# RASPILOTv1_0.net
KiCad netlist of a schematic drawn in EAGLE
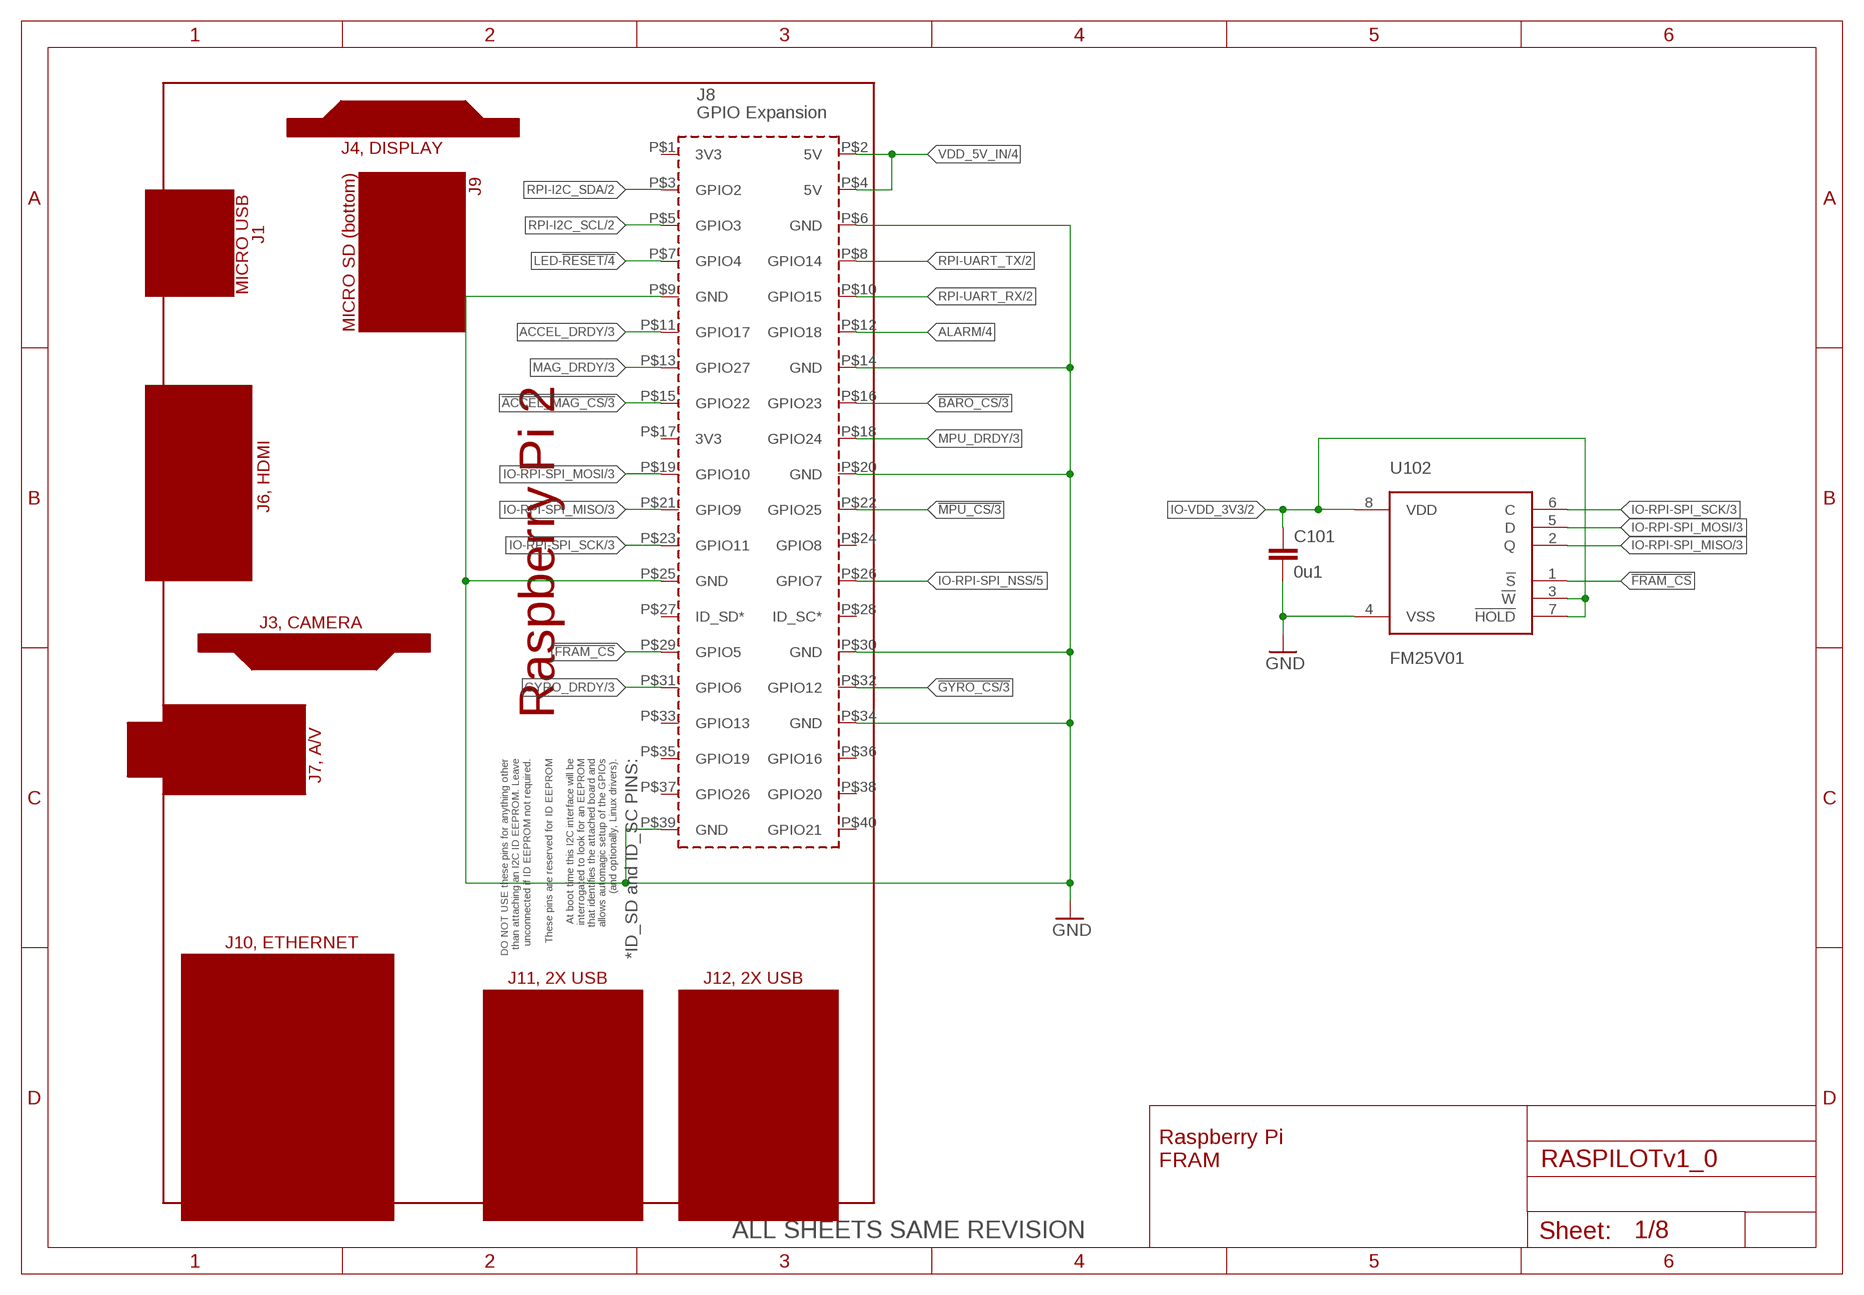
[diagram p0: schematic, sheet 1]
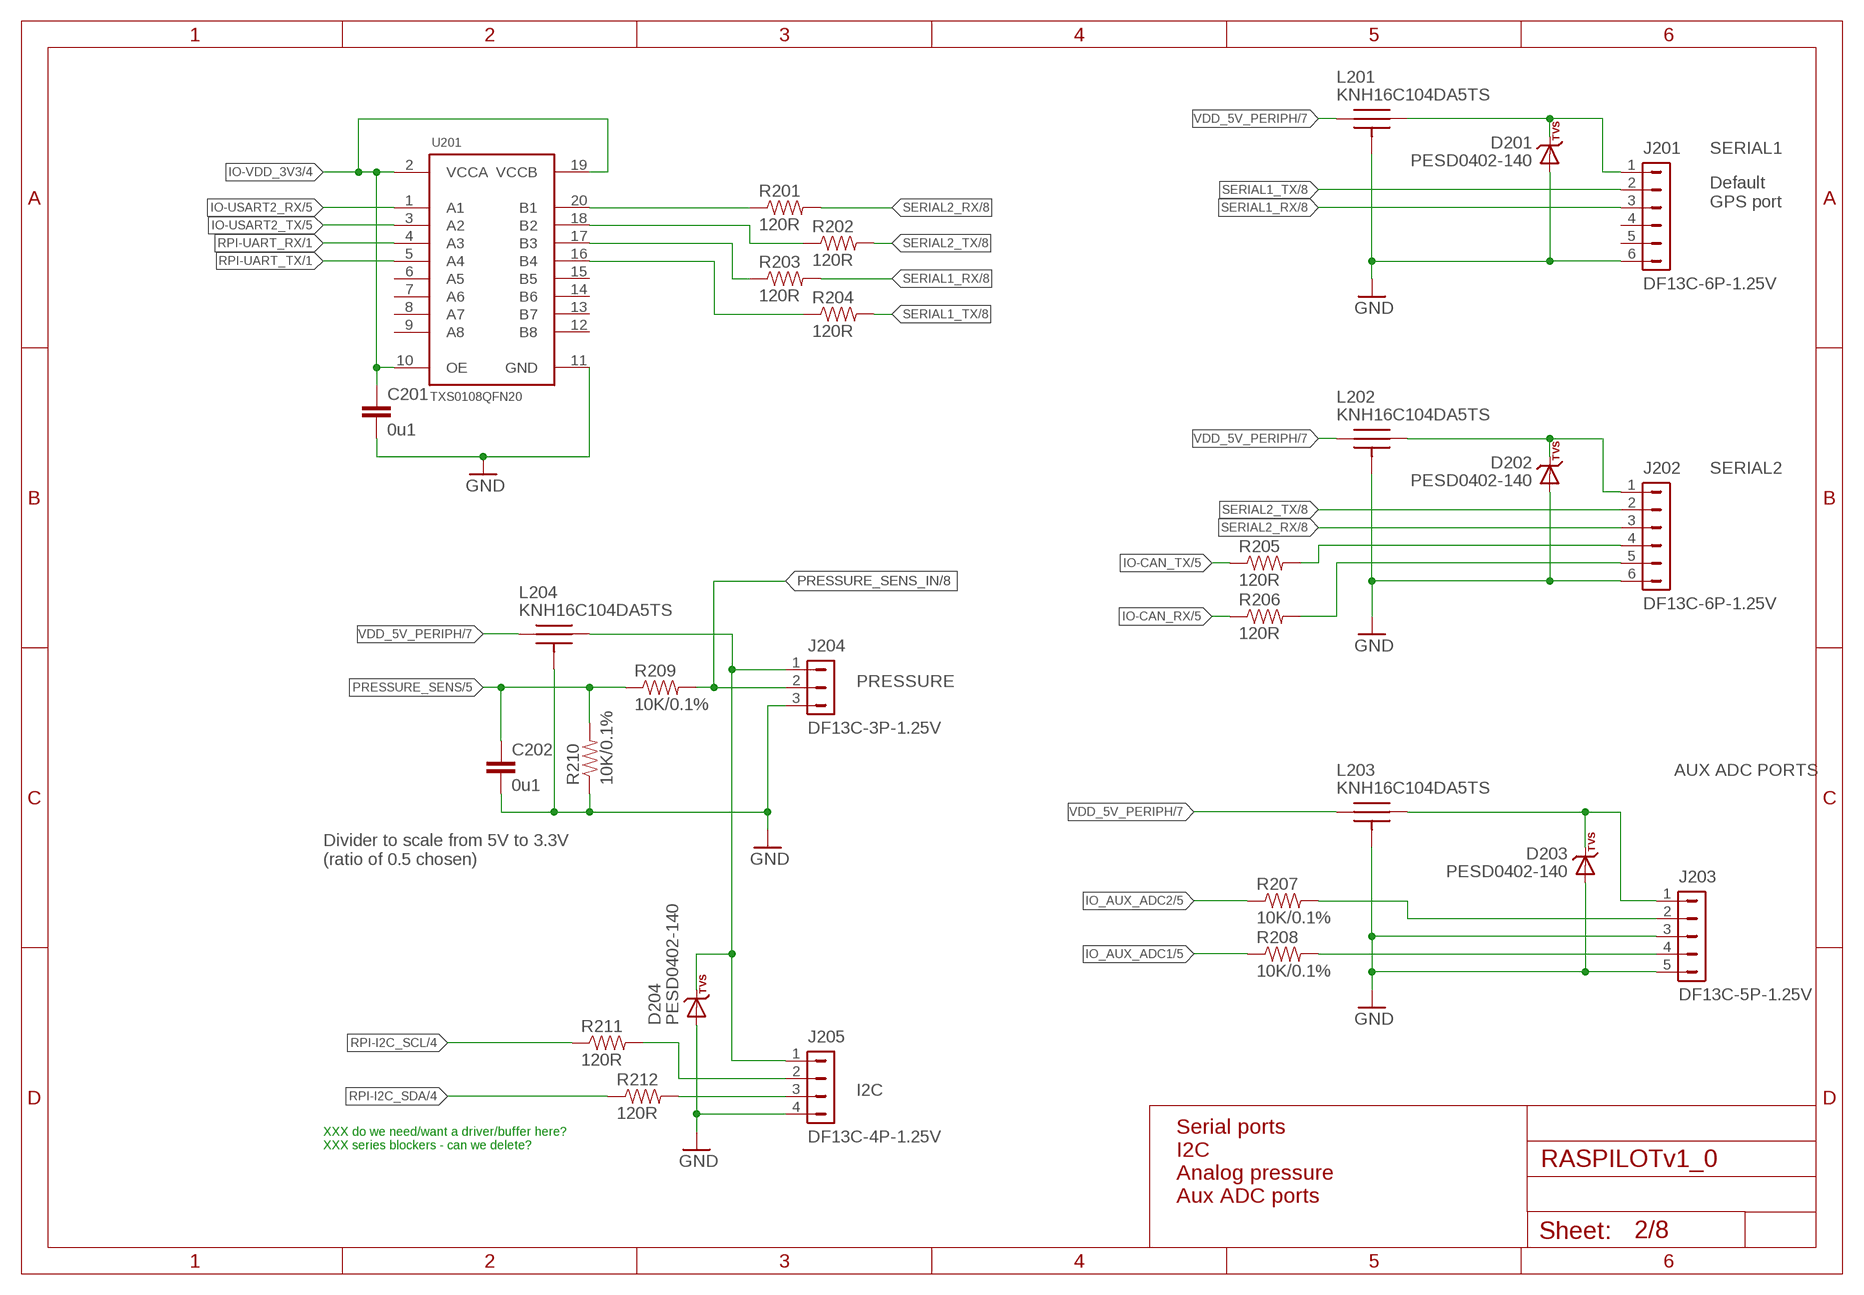
[diagram p1: schematic, sheet 2]
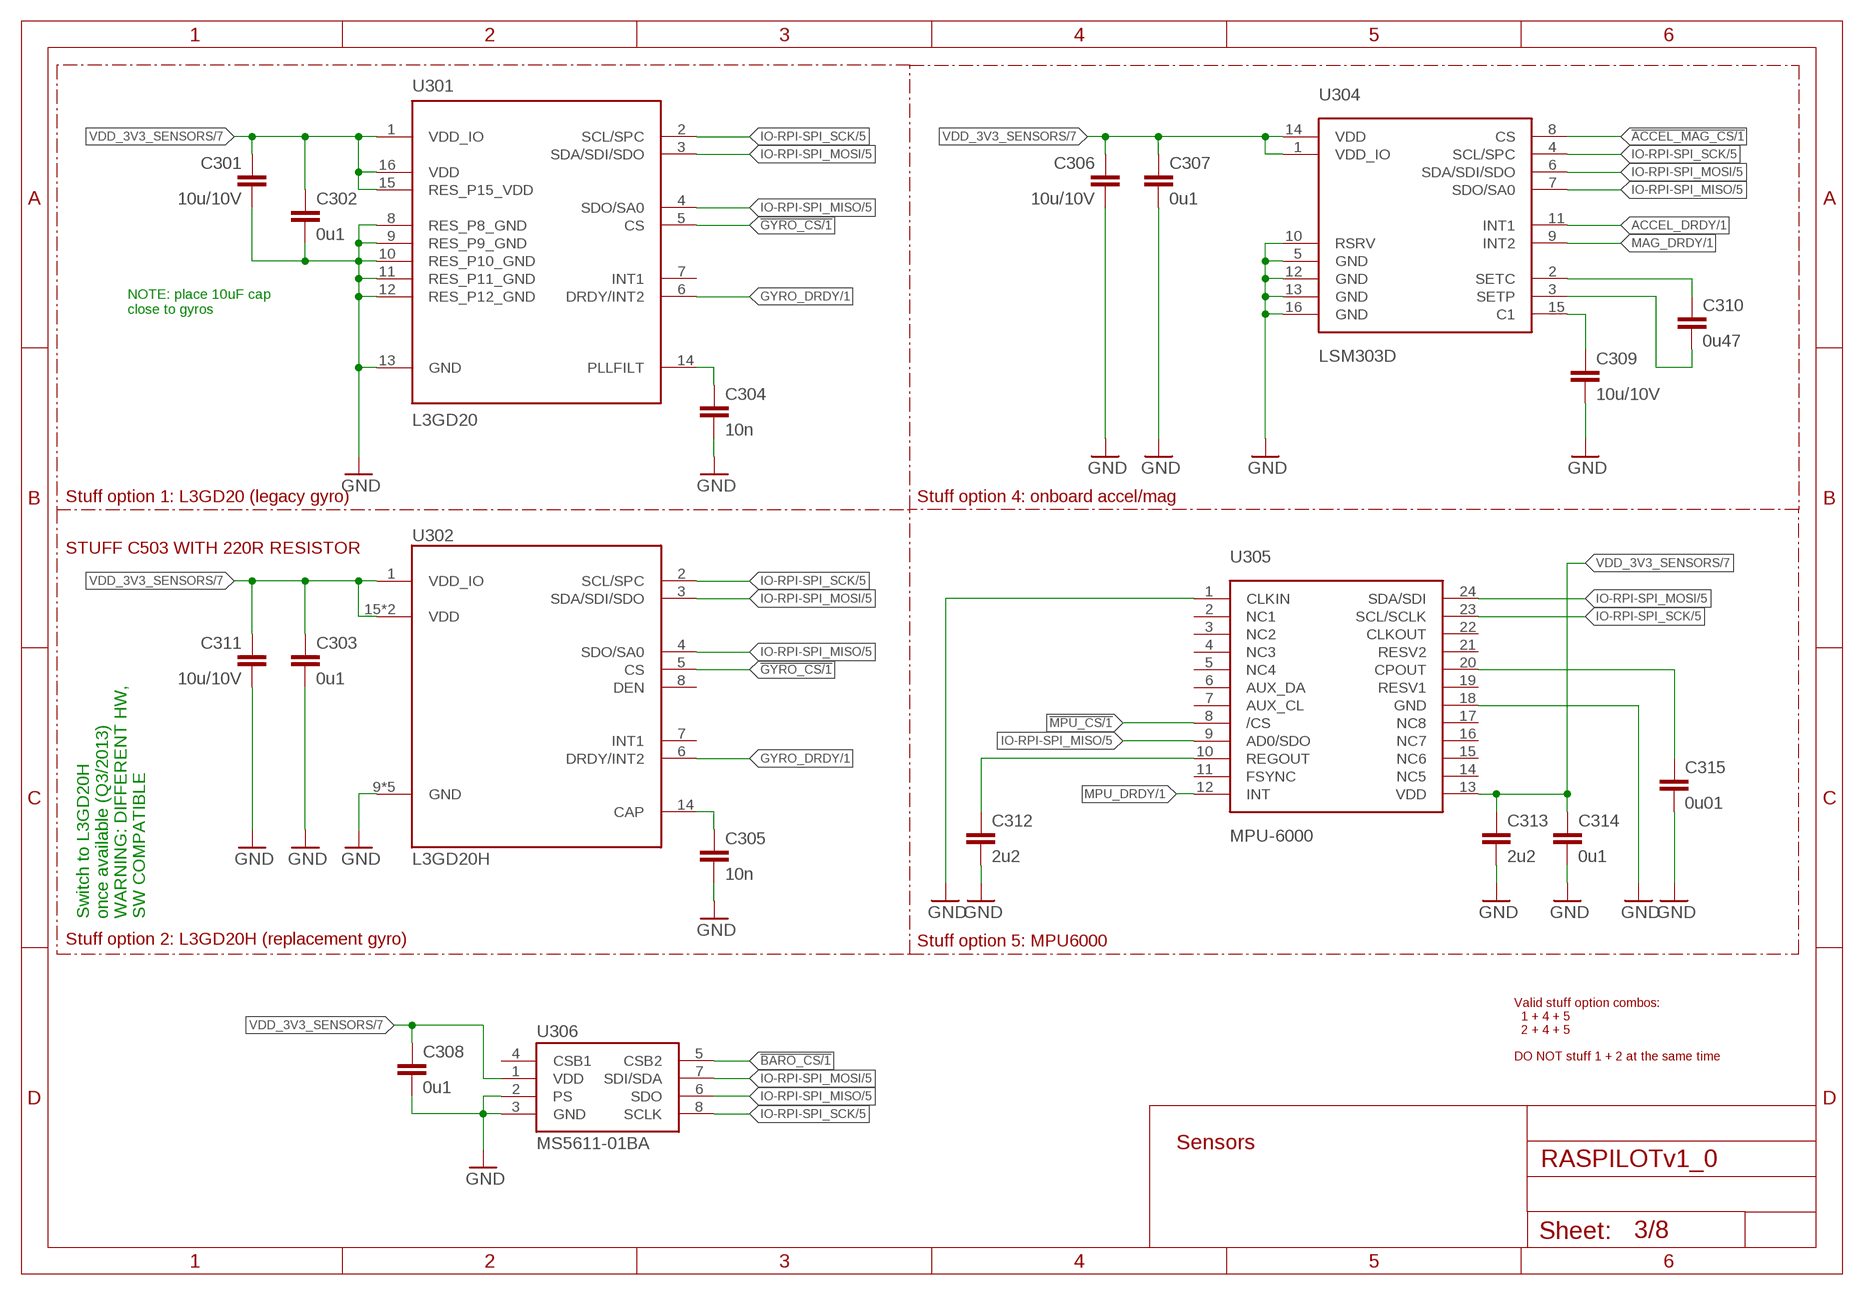
[diagram p2: schematic, sheet 3]
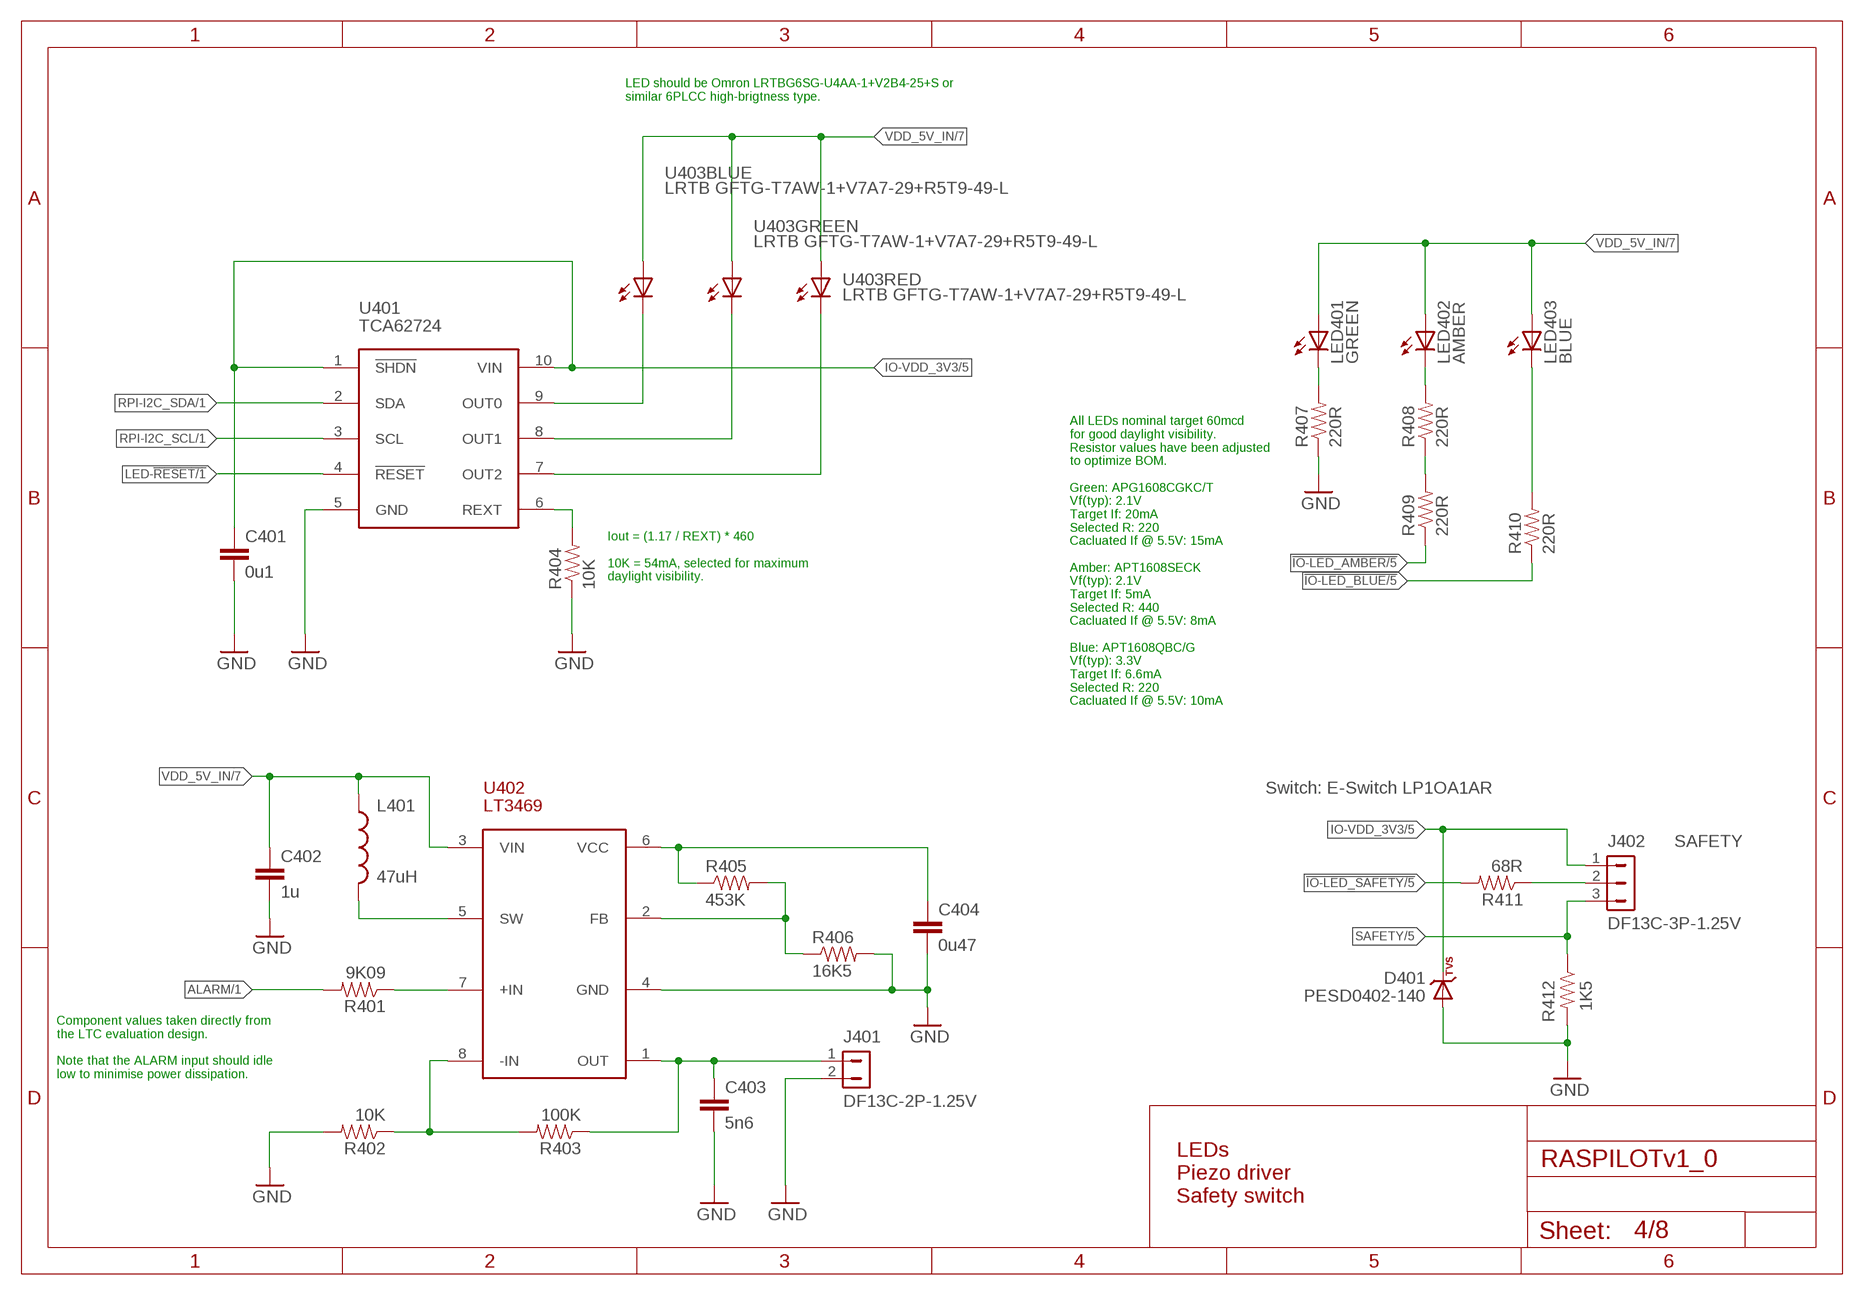
[diagram p3: schematic, sheet 4]
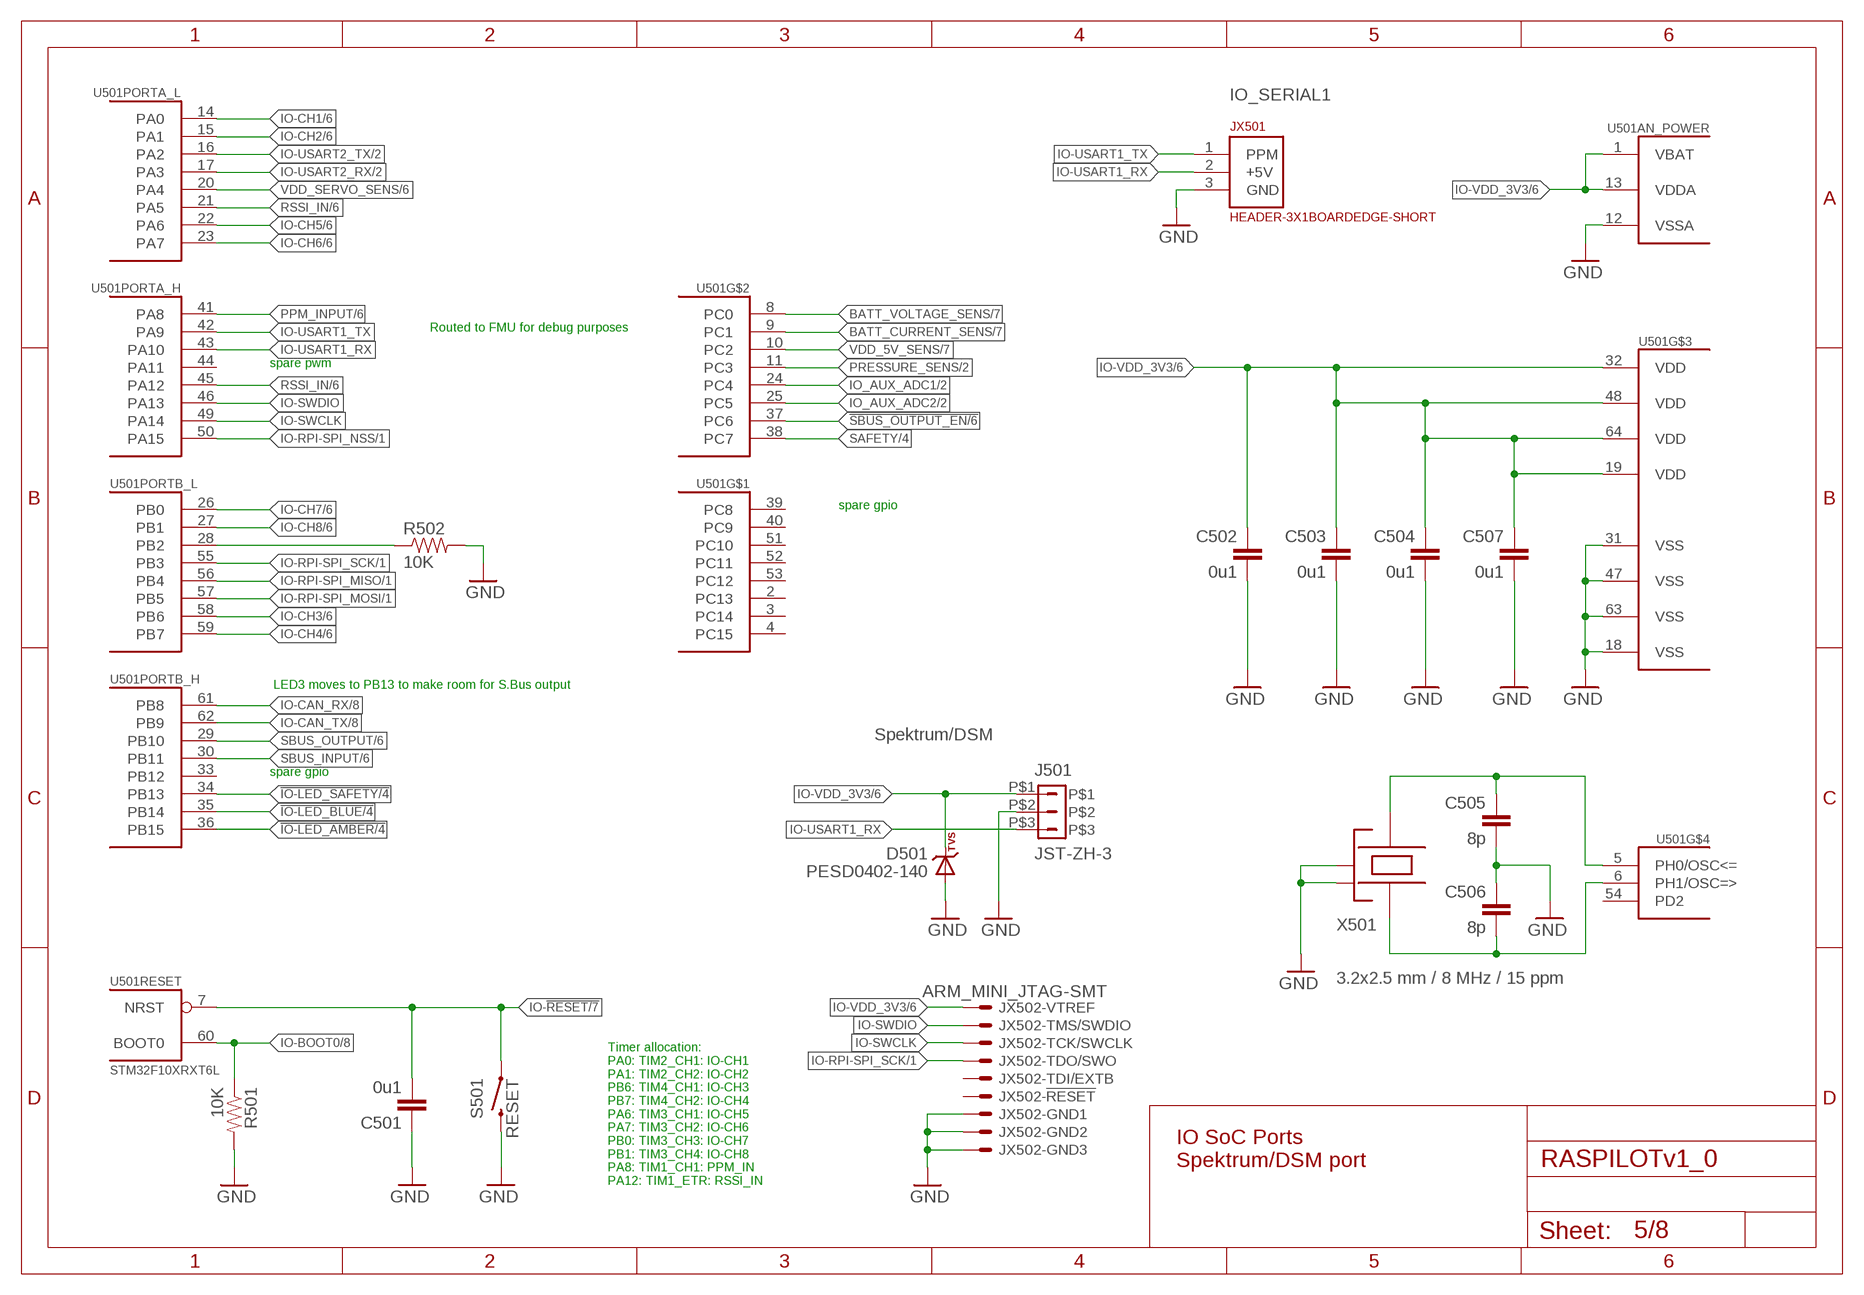
[diagram p4: schematic, sheet 5]
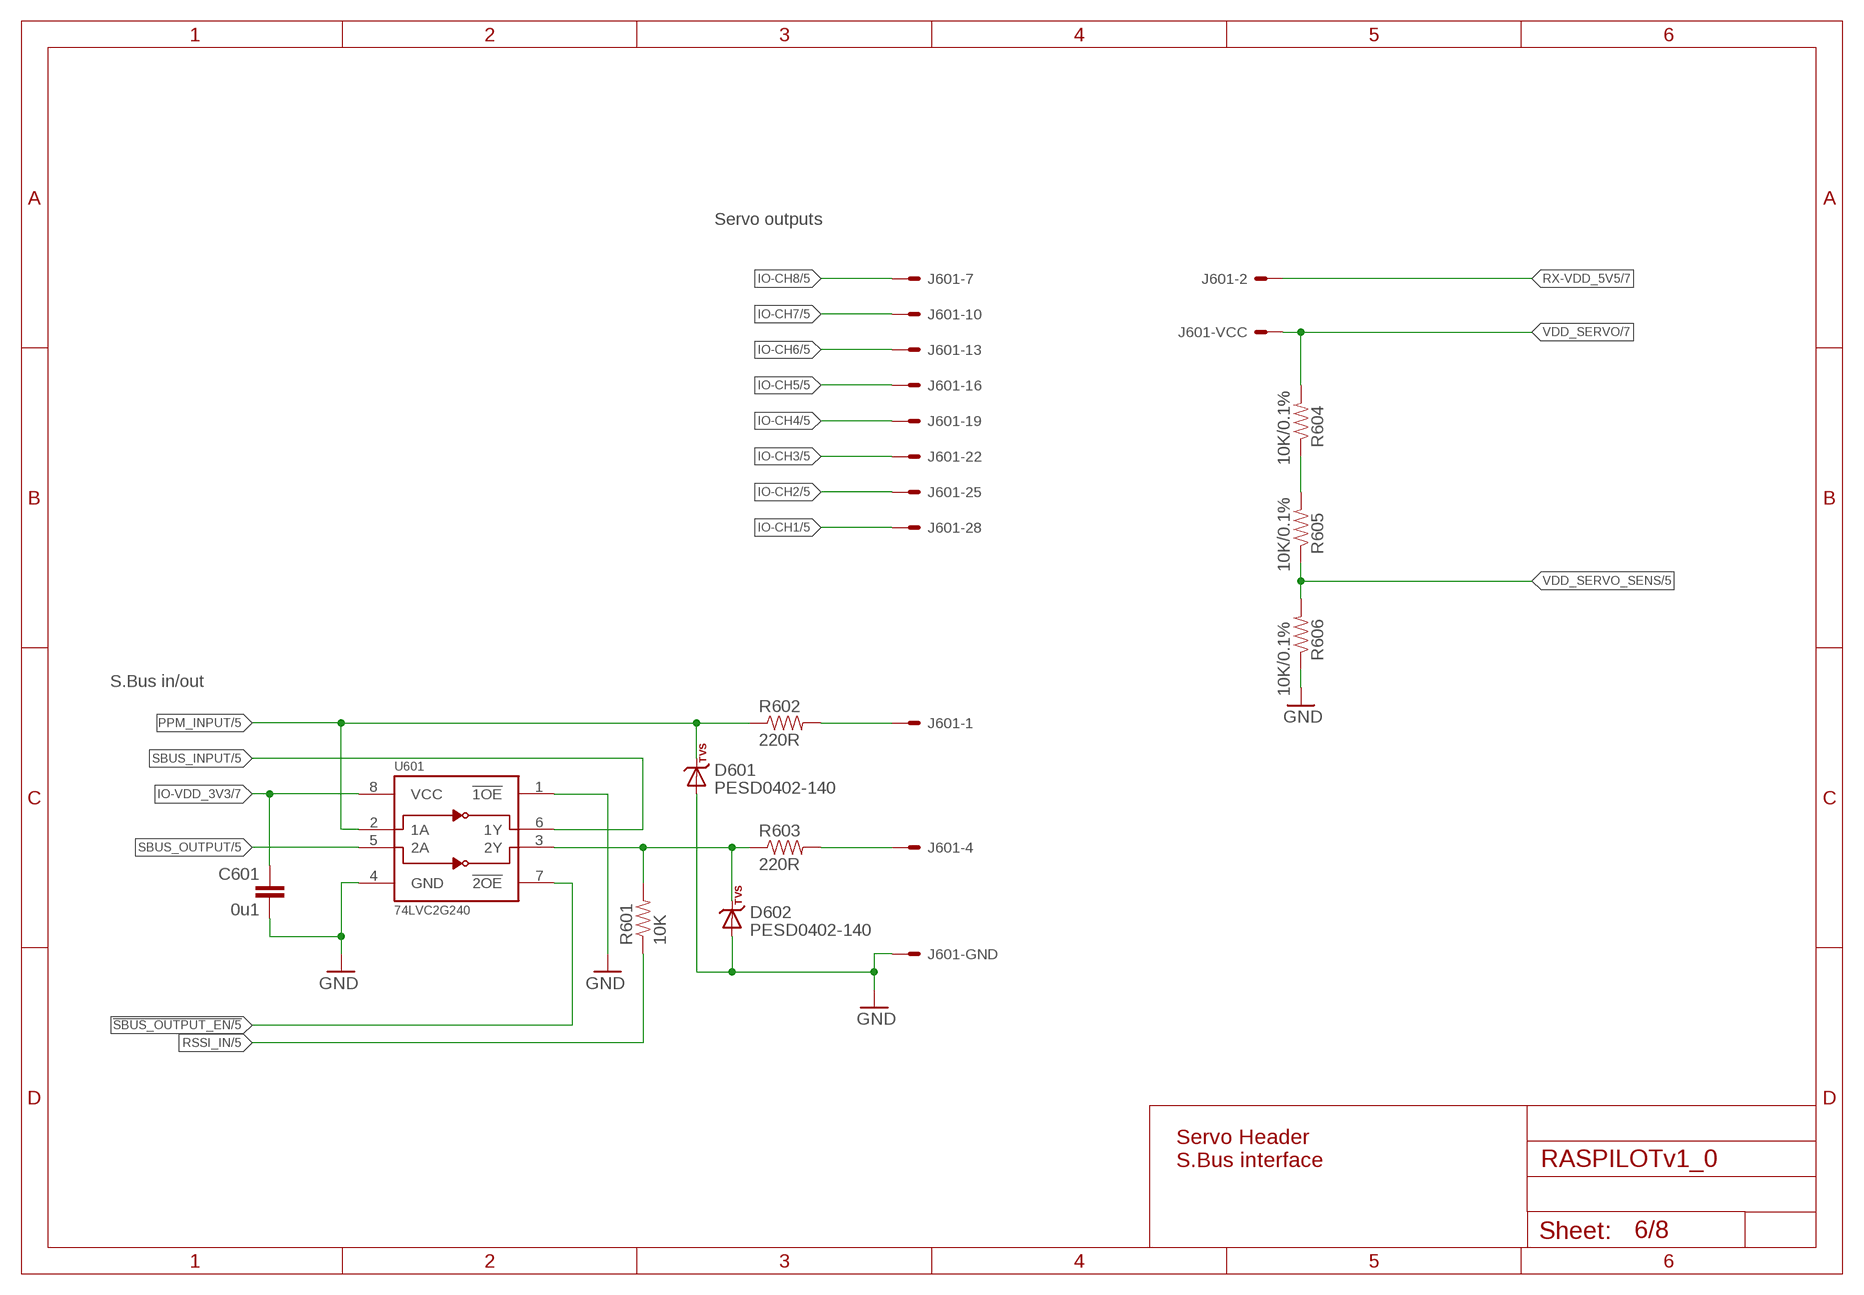
[diagram p5: schematic, sheet 6]
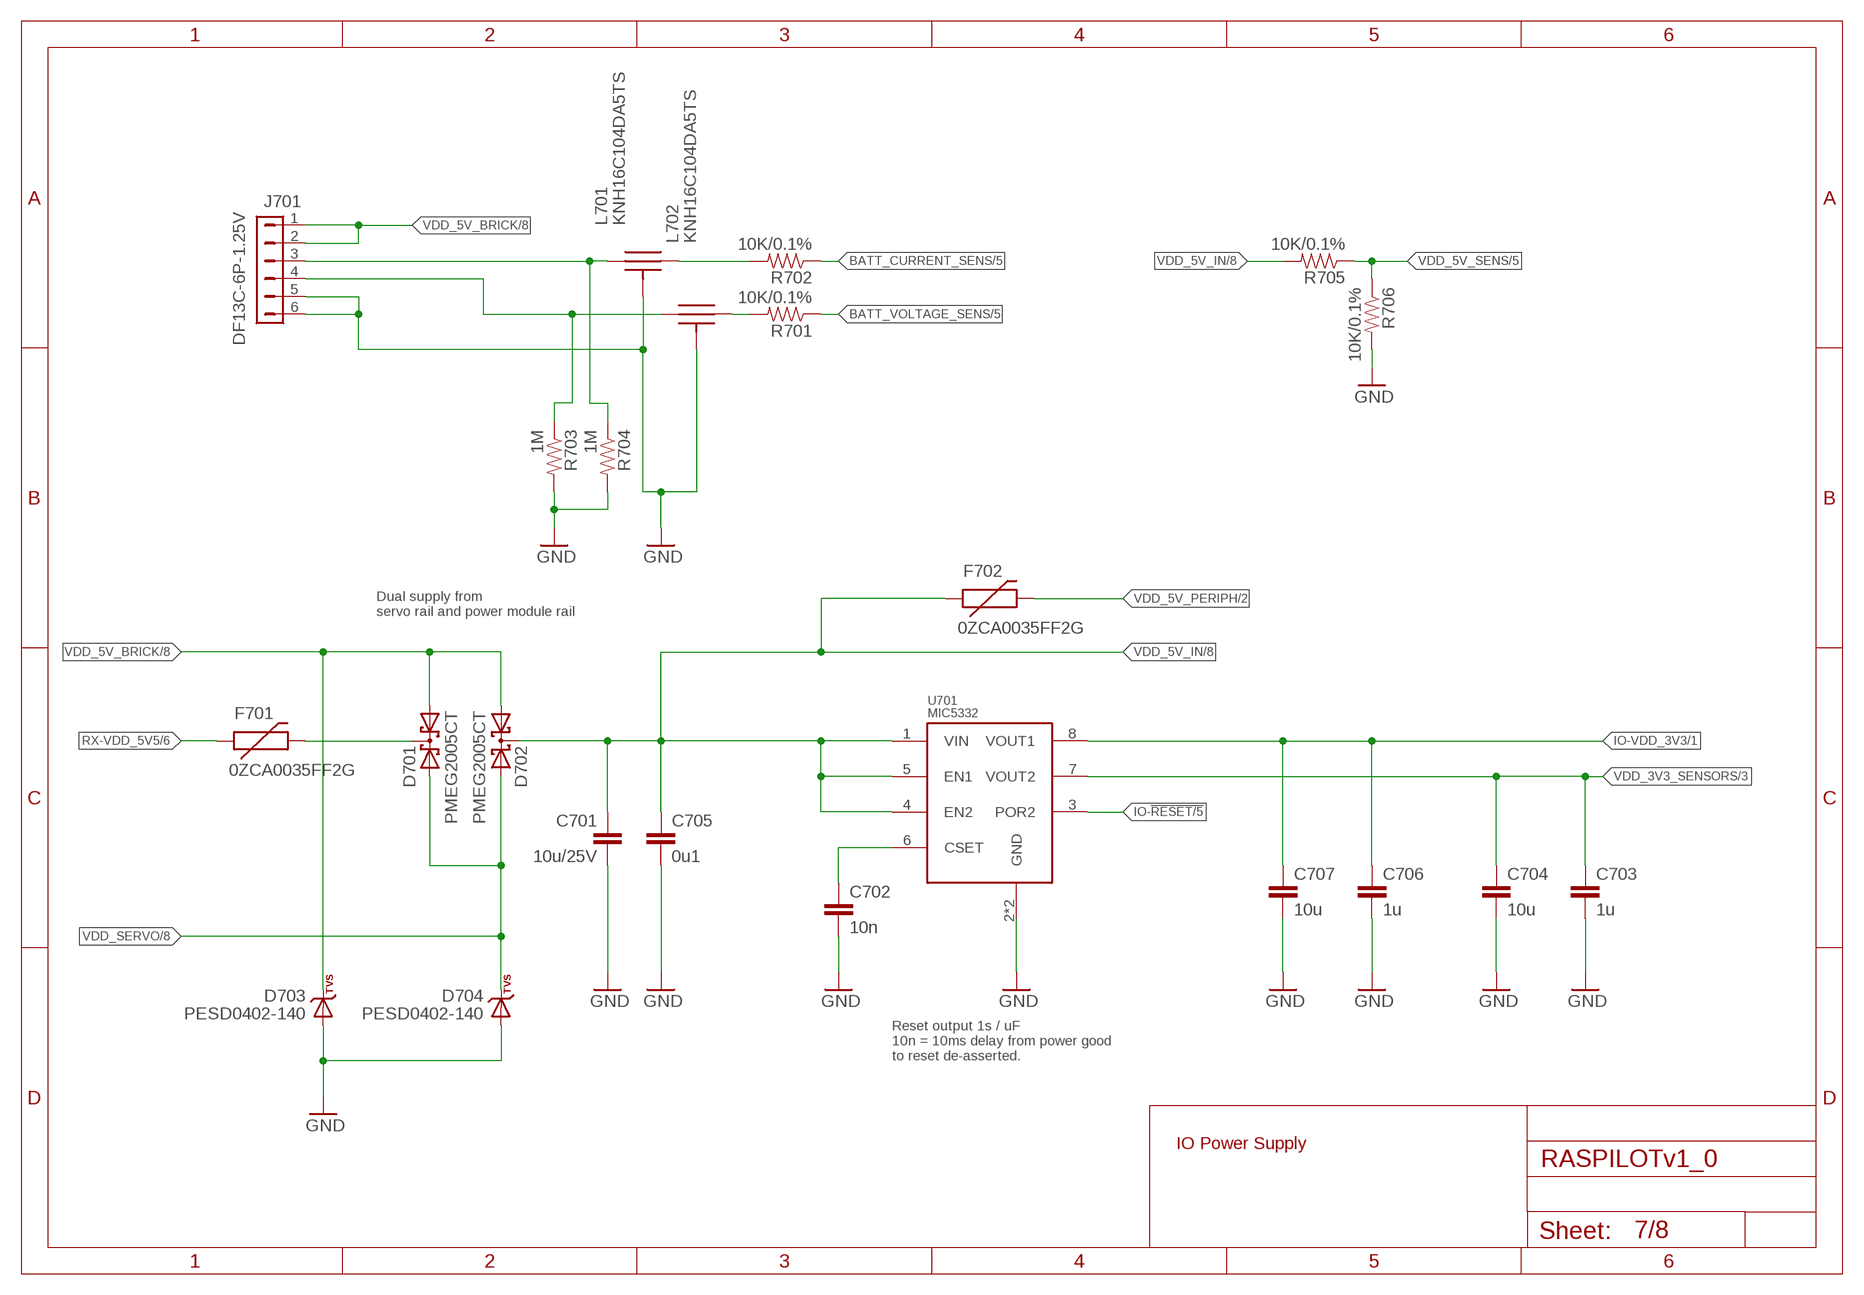
[diagram p6: schematic, sheet 7]
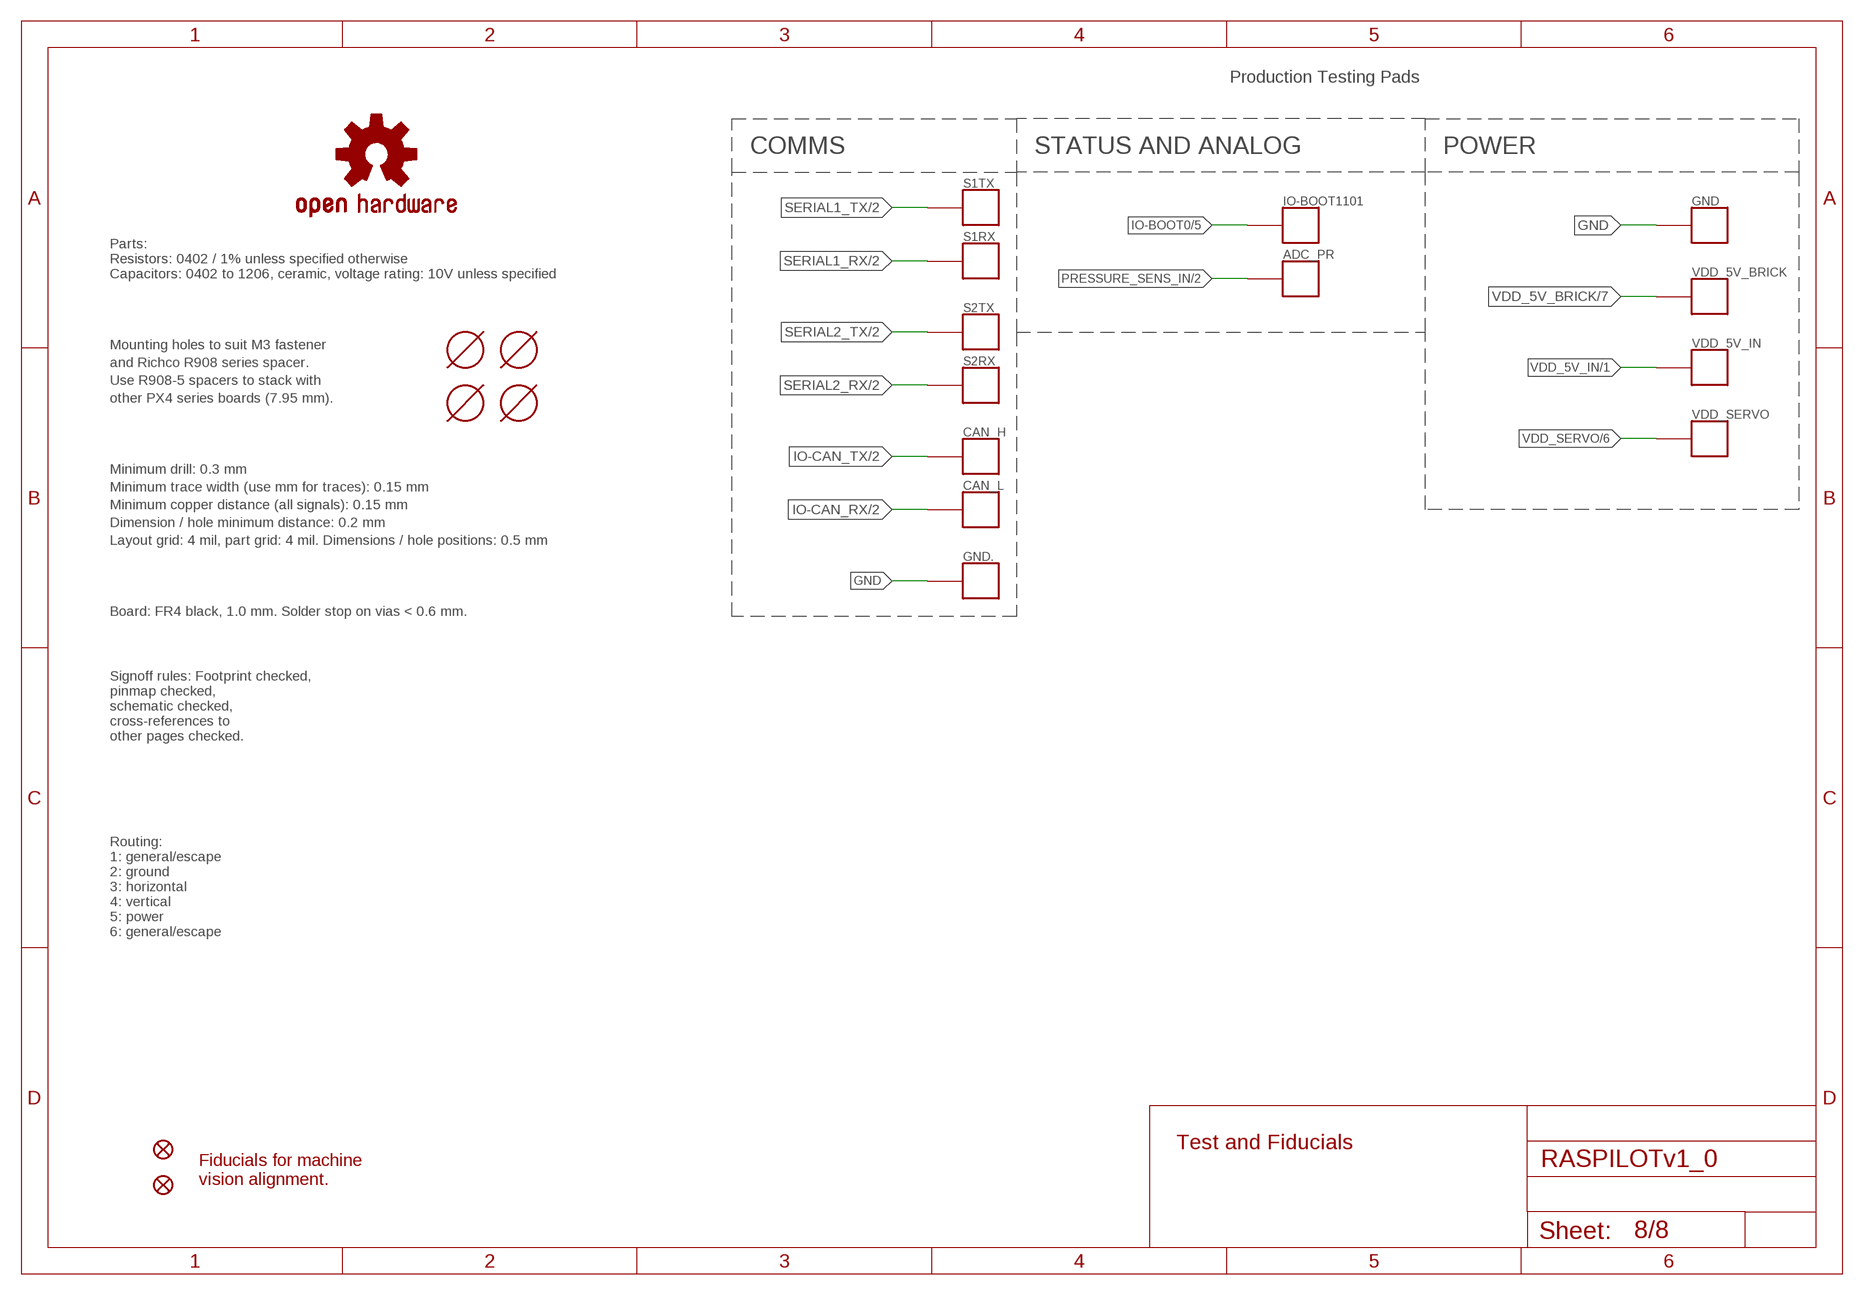
[diagram p7: schematic, sheet 8]

(export (version "E")
  (design (tool "Eeschema 10.0.6"))
  (components
    (comp (ref "C301")
      (value "10u/10V")
      (footprint "eagle-import:0805-CAP")
      (fields (field (name "PARTNO") "CC0805ZKY5V6BB106"))
      (libsource (lib "eagle-import") (part "CAP0805"))
    )
    (comp (ref "C302")
      (value "0u1")
      (footprint "eagle-import:0402-CAP")
      (fields (field (name "PARTNO") "CC0402ZRY5V7BB104"))
      (libsource (lib "eagle-import") (part "CAP0402"))
    )
    (comp (ref "C303")
      (value "0u1")
      (footprint "eagle-import:0402-CAP")
      (fields (field (name "PARTNO") "CC0402ZRY5V7BB104"))
      (libsource (lib "eagle-import") (part "CAP0402"))
    )
    (comp (ref "C304")
      (value "10n")
      (footprint "eagle-import:0402-CAP")
      (fields (field (name "PARTNO") "CC0402KRX7R7BB103"))
      (libsource (lib "eagle-import") (part "CAP0402"))
    )
    (comp (ref "C305")
      (value "10n")
      (footprint "eagle-import:0402-CAP")
      (fields (field (name "PARTNO") "CC0402KRX7R7BB103"))
      (libsource (lib "eagle-import") (part "CAP0402"))
    )
    (comp (ref "C306")
      (value "10u/10V")
      (footprint "eagle-import:0805-CAP")
      (fields (field (name "PARTNO") "CC0805ZKY5V6BB106"))
      (libsource (lib "eagle-import") (part "CAP0805"))
    )
    (comp (ref "C307")
      (value "0u1")
      (footprint "eagle-import:0402-CAP")
      (fields (field (name "PARTNO") "CC0402ZRY5V7BB104"))
      (libsource (lib "eagle-import") (part "CAP0402"))
    )
    (comp (ref "C308")
      (value "0u1")
      (footprint "eagle-import:0402-CAP")
      (fields (field (name "PARTNO") "CC0402ZRY5V7BB104"))
      (libsource (lib "eagle-import") (part "CAP0402"))
    )
    (comp (ref "C309")
      (value "10u/10V")
      (footprint "eagle-import:0805-CAP")
      (fields (field (name "PARTNO") "CC0805ZKY5V6BB106"))
      (libsource (lib "eagle-import") (part "CAP0805"))
    )
    (comp (ref "C310")
      (value "0u47")
      (footprint "eagle-import:0402-CAP")
      (fields (field (name "PARTNO") "C1005X5R1C474K050BC"))
      (libsource (lib "eagle-import") (part "CAP0402"))
    )
    (comp (ref "C311")
      (value "10u/10V")
      (footprint "eagle-import:0805-CAP")
      (fields (field (name "PARTNO") "CC0805ZKY5V6BB106"))
      (libsource (lib "eagle-import") (part "CAP0805"))
    )
    (comp (ref "C312")
      (value "2u2")
      (footprint "eagle-import:0603-CAP")
      (fields (field (name "PARTNO") "C1608X6S1C225K080AC"))
      (libsource (lib "eagle-import") (part "CAP0603"))
    )
    (comp (ref "C313")
      (value "2u2")
      (footprint "eagle-import:0603-CAP")
      (fields (field (name "PARTNO") "C1608X6S1C225K080AC"))
      (libsource (lib "eagle-import") (part "CAP0603"))
    )
    (comp (ref "C314")
      (value "0u1")
      (footprint "eagle-import:0402-CAP")
      (fields (field (name "PARTNO") "CC0402ZRY5V7BB104"))
      (libsource (lib "eagle-import") (part "CAP0402"))
    )
    (comp (ref "C315")
      (value "0u01")
      (footprint "eagle-import:0603-CAP")
      (fields (field (name "PARTNO") "06033C103JAT2A"))
      (libsource (lib "eagle-import") (part "CAP0603"))
    )
    (comp (ref "U301")
      (value "L3GD20")
      (footprint "eagle-import:L3G4200DH-MAN")
      (libsource (lib "eagle-import") (part "L3G4200DH-LL"))
    )
    (comp (ref "U302")
      (value "L3GD20H")
      (footprint "eagle-import:LGA-16L")
      (libsource (lib "eagle-import") (part "L3GD20H"))
    )
    (comp (ref "U304")
      (value "LSM303D")
      (footprint "eagle-import:LGA-16L")
      (libsource (lib "eagle-import") (part "LSM303D"))
    )
    (comp (ref "U305")
      (value "MPU-6000")
      (footprint "eagle-import:QFN-24")
      (libsource (lib "eagle-import") (part "MPU-6000"))
    )
    (comp (ref "U306")
      (value "MS5611-01BA")
      (footprint "eagle-import:MS5611-01BA")
      (libsource (lib "eagle-import") (part "MS5611-01BA"))
    )
    (comp (ref "C601")
      (value "0u1")
      (footprint "eagle-import:0402-CAP")
      (fields (field (name "PARTNO") "CC0402ZRY5V7BB104"))
      (libsource (lib "eagle-import") (part "CAP0402"))
    )
    (comp (ref "D601")
      (value "PESD0402-140")
      (footprint "eagle-import:0402-TVS")
      (libsource (lib "eagle-import") (part "DIODE-TVS"))
    )
    (comp (ref "D602")
      (value "PESD0402-140")
      (footprint "eagle-import:0402-TVS")
      (libsource (lib "eagle-import") (part "DIODE-TVS"))
    )
    (comp (ref "J601")
      (value "HEADER-3X10")
      (footprint "eagle-import:3X10RA")
      (libsource (lib "eagle-import") (part "HEADER-3X10"))
    )
    (comp (ref "R601")
      (value "10K")
      (footprint "eagle-import:0402-RES")
      (fields (field (name "PARTNO") "RC0402FR-0710KL"))
      (libsource (lib "eagle-import") (part "RESISTOR0402-RES"))
    )
    (comp (ref "R602")
      (value "220R")
      (footprint "eagle-import:0402-RES")
      (fields (field (name "PARTNO") "RC0402FR-07220RL"))
      (libsource (lib "eagle-import") (part "RESISTOR0402-RES"))
    )
    (comp (ref "R603")
      (value "220R")
      (footprint "eagle-import:0402-RES")
      (fields (field (name "PARTNO") "RC0402FR-07220RL"))
      (libsource (lib "eagle-import") (part "RESISTOR0402-RES"))
    )
    (comp (ref "R604")
      (value "10K/0.1%")
      (footprint "eagle-import:0402-RES")
      (fields (field (name "PARTNO") "ERA-2AEB103X"))
      (libsource (lib "eagle-import") (part "RESISTOR0402-RES"))
    )
    (comp (ref "R605")
      (value "10K/0.1%")
      (footprint "eagle-import:0402-RES")
      (fields (field (name "PARTNO") "ERA-2AEB103X"))
      (libsource (lib "eagle-import") (part "RESISTOR0402-RES"))
    )
    (comp (ref "R606")
      (value "10K/0.1%")
      (footprint "eagle-import:0402-RES")
      (fields (field (name "PARTNO") "ERA-2AEB103X"))
      (libsource (lib "eagle-import") (part "RESISTOR0402-RES"))
    )
    (comp (ref "U601")
      (value "74LVC2G240")
      (footprint "eagle-import:TSSOP8_SOT505-2")
      (fields (field (name "PARTNO") "74LVC2G240DP,125"))
      (libsource (lib "eagle-import") (part "74LVC2G240-TSSOP-8"))
    )
    (comp (ref "C101")
      (value "0u1")
      (footprint "eagle-import:0402-CAP")
      (fields (field (name "PARTNO") "CC0402ZRY5V7BB104"))
      (libsource (lib "eagle-import") (part "CAP0402"))
    )
    (comp (ref "U101")
      (value "RPI2")
      (footprint "eagle-import:RPI2")
      (libsource (lib "eagle-import") (part "RPI2"))
    )
    (comp (ref "U102")
      (value "FM25V01")
      (footprint "eagle-import:SO08")
      (fields (field (name "PARTNO") "FM25V01-G"))
      (libsource (lib "eagle-import") (part "FM25V01"))
    )
    (comp (ref "C701")
      (value "10u/25V")
      (footprint "eagle-import:0805-CAP")
      (fields (field (name "PARTNO") "CL21A106KAYNNNE"))
      (libsource (lib "eagle-import") (part "CAP0805"))
    )
    (comp (ref "C702")
      (value "10n")
      (footprint "eagle-import:0402-CAP")
      (fields (field (name "PARTNO") "CC0402KRX7R7BB103"))
      (libsource (lib "eagle-import") (part "CAP0402"))
    )
    (comp (ref "C703")
      (value "1u")
      (footprint "eagle-import:0603-CAP")
      (fields (field (name "PARTNO") "CC0603ZRY5V7BB105"))
      (libsource (lib "eagle-import") (part "CAP0603"))
    )
    (comp (ref "C704")
      (value "10u")
      (footprint "eagle-import:0603-CAP")
      (fields (field (name "PARTNO") "C1608X5R1A106K080AC"))
      (libsource (lib "eagle-import") (part "CAP0603"))
    )
    (comp (ref "C705")
      (value "0u1")
      (footprint "eagle-import:0402-CAP")
      (fields (field (name "PARTNO") "CC0402ZRY5V7BB104"))
      (libsource (lib "eagle-import") (part "CAP0402"))
    )
    (comp (ref "C706")
      (value "1u")
      (footprint "eagle-import:0603-CAP")
      (fields (field (name "PARTNO") "CC0603ZRY5V7BB105"))
      (libsource (lib "eagle-import") (part "CAP0603"))
    )
    (comp (ref "C707")
      (value "10u")
      (footprint "eagle-import:0603-CAP")
      (fields (field (name "PARTNO") "C1608X5R1A106K080AC"))
      (libsource (lib "eagle-import") (part "CAP0603"))
    )
    (comp (ref "D701")
      (value "PMEG2005CT")
      (footprint "eagle-import:SOT23-3")
      (libsource (lib "eagle-import") (part "PMEG2005CT"))
    )
    (comp (ref "D702")
      (value "PMEG2005CT")
      (footprint "eagle-import:SOT23-3")
      (libsource (lib "eagle-import") (part "PMEG2005CT"))
    )
    (comp (ref "D703")
      (value "PESD0402-140")
      (footprint "eagle-import:0402-TVS")
      (libsource (lib "eagle-import") (part "DIODE-TVS"))
    )
    (comp (ref "D704")
      (value "PESD0402-140")
      (footprint "eagle-import:0402-TVS")
      (libsource (lib "eagle-import") (part "DIODE-TVS"))
    )
    (comp (ref "F701")
      (value "0ZCA0035FF2G")
      (footprint "eagle-import:PTC-1206")
      (libsource (lib "eagle-import") (part "PTCSMD"))
    )
    (comp (ref "F702")
      (value "0ZCA0035FF2G")
      (footprint "eagle-import:PTC-1206")
      (libsource (lib "eagle-import") (part "PTCSMD"))
    )
    (comp (ref "J701")
      (value "DF13C-6P-1.25V")
      (footprint "eagle-import:DF13C-6P-1.25V")
      (fields (field (name "PARTNO") "DF13C-6P-1.25V(20)"))
      (libsource (lib "eagle-import") (part "DF13-6P-1.25V"))
    )
    (comp (ref "L701")
      (value "KNH16C104DA5TS")
      (footprint "eagle-import:KYOCERA-KNH16-DA")
      (libsource (lib "eagle-import") (part "KNH16C104DA5TS"))
    )
    (comp (ref "L702")
      (value "KNH16C104DA5TS")
      (footprint "eagle-import:KYOCERA-KNH16-DA")
      (libsource (lib "eagle-import") (part "KNH16C104DA5TS"))
    )
    (comp (ref "R701")
      (value "10K/0.1%")
      (footprint "eagle-import:0402-RES")
      (fields (field (name "PARTNO") "ERA-2AEB103X"))
      (libsource (lib "eagle-import") (part "RESISTOR0402-RES"))
    )
    (comp (ref "R702")
      (value "10K/0.1%")
      (footprint "eagle-import:0402-RES")
      (fields (field (name "PARTNO") "ERA-2AEB103X"))
      (libsource (lib "eagle-import") (part "RESISTOR0402-RES"))
    )
    (comp (ref "R703")
      (value "1M")
      (footprint "eagle-import:0402-RES")
      (fields (field (name "PARTNO") "RC0402FR-071ML"))
      (libsource (lib "eagle-import") (part "RESISTOR0402-RES"))
    )
    (comp (ref "R704")
      (value "1M")
      (footprint "eagle-import:0402-RES")
      (fields (field (name "PARTNO") "RC0402FR-071ML"))
      (libsource (lib "eagle-import") (part "RESISTOR0402-RES"))
    )
    (comp (ref "R705")
      (value "10K/0.1%")
      (footprint "eagle-import:0402-RES")
      (fields (field (name "PARTNO") "ERA-2AEB103X"))
      (libsource (lib "eagle-import") (part "RESISTOR0402-RES"))
    )
    (comp (ref "R706")
      (value "10K/0.1%")
      (footprint "eagle-import:0402-RES")
      (fields (field (name "PARTNO") "ERA-2AEB103X"))
      (libsource (lib "eagle-import") (part "RESISTOR0402-RES"))
    )
    (comp (ref "U701")
      (value "MIC5332")
      (footprint "eagle-import:MLF-8-EPAD")
      (fields (field (name "PARTNO") "MIC5332-SSYMT"))
      (libsource (lib "eagle-import") (part "MIC5332"))
    )
    (comp (ref "C501")
      (value "0u1")
      (footprint "eagle-import:0402-CAP")
      (fields (field (name "PARTNO") "CC0402ZRY5V7BB104"))
      (libsource (lib "eagle-import") (part "CAP0402"))
    )
    (comp (ref "C502")
      (value "0u1")
      (footprint "eagle-import:0402-CAP")
      (fields (field (name "PARTNO") "CC0402ZRY5V7BB104"))
      (libsource (lib "eagle-import") (part "CAP0402"))
    )
    (comp (ref "C503")
      (value "0u1")
      (footprint "eagle-import:0402-CAP")
      (fields (field (name "PARTNO") "CC0402ZRY5V7BB104"))
      (libsource (lib "eagle-import") (part "CAP0402"))
    )
    (comp (ref "C504")
      (value "0u1")
      (footprint "eagle-import:0402-CAP")
      (fields (field (name "PARTNO") "CC0402ZRY5V7BB104"))
      (libsource (lib "eagle-import") (part "CAP0402"))
    )
    (comp (ref "C505")
      (value "8p")
      (footprint "eagle-import:0402-CAP")
      (fields (field (name "PARTNO") "C1005C0G1H080C"))
      (libsource (lib "eagle-import") (part "CAP0402"))
    )
    (comp (ref "C506")
      (value "8p")
      (footprint "eagle-import:0402-CAP")
      (fields (field (name "PARTNO") "C1005C0G1H080C"))
      (libsource (lib "eagle-import") (part "CAP0402"))
    )
    (comp (ref "C507")
      (value "0u1")
      (footprint "eagle-import:0402-CAP")
      (fields (field (name "PARTNO") "CC0402ZRY5V7BB104"))
      (libsource (lib "eagle-import") (part "CAP0402"))
    )
    (comp (ref "D501")
      (value "PESD0402-140")
      (footprint "eagle-import:0402-TVS")
      (libsource (lib "eagle-import") (part "DIODE-TVS"))
    )
    (comp (ref "J501")
      (value "JST-ZH-3")
      (footprint "eagle-import:JST-ZH-SMT-VERTICAL")
      (fields (field (name "PARTNO") "B3B-ZR-SM4-TF (LF)(SN)(P)"))
      (libsource (lib "eagle-import") (part "JST-ZH-3"))
    )
    (comp (ref "JX501")
      (value "HEADER-3X1BOARDEDGE-SHORT")
      (footprint "eagle-import:HEADER_3X01_SMD_H_BOARD_EDGE_SHORT")
      (libsource (lib "eagle-import") (part "HEADER-3X1BOARDEDGE-SHORT"))
    )
    (comp (ref "JX502")
      (value "ARM_MINI_JTAG-SMT")
      (footprint "eagle-import:FTSH-105-01-XXX-DV-K")
      (fields (field (name "BOM") "EXCLUDE") (field (name "PARTNO") "M50-3900542"))
      (libsource (lib "eagle-import") (part "ARM_MINI_JTAG-SMT"))
    )
    (comp (ref "R501")
      (value "10K")
      (footprint "eagle-import:0402-RES")
      (fields (field (name "PARTNO") "RC0402FR-0710KL"))
      (libsource (lib "eagle-import") (part "RESISTOR0402-RES"))
    )
    (comp (ref "R502")
      (value "10K")
      (footprint "eagle-import:0402-RES")
      (fields (field (name "PARTNO") "RC0402FR-0710KL"))
      (libsource (lib "eagle-import") (part "RESISTOR0402-RES"))
    )
    (comp (ref "S501")
      (value "RESET")
      (footprint "eagle-import:EVQP7J01K")
      (fields (field (name "PARTNO") "EVQ-P7J01P"))
      (libsource (lib "eagle-import") (part "SWITCH-MOMENTARY-2"))
    )
    (comp (ref "U501")
      (value "STM32F10XRXT6L")
      (footprint "eagle-import:TQFP64")
      (libsource (lib "eagle-import") (part "STM32F10XRXT6L"))
    )
    (comp (ref "X501")
      (value "3.2x2.5 mm / 8 MHz / 15 ppm")
      (footprint "eagle-import:OSCILLATOR-3.2X2.5")
      (fields (field (name "PARTNO") "NX3225SA-24.000000MHZ"))
      (libsource (lib "eagle-import") (part "OSCILLATOR-3.2X2.5"))
    )
    (comp (ref "ADC_PR")
      (value "PAD.04")
      (footprint "eagle-import:PAD.04X.04")
      (libsource (lib "eagle-import") (part "PAD.04"))
    )
    (comp (ref "CAN_H")
      (value "PAD.04")
      (footprint "eagle-import:PAD.04X.04")
      (libsource (lib "eagle-import") (part "PAD.04"))
    )
    (comp (ref "CAN_L")
      (value "PAD.04")
      (footprint "eagle-import:PAD.04X.04")
      (libsource (lib "eagle-import") (part "PAD.04"))
    )
    (comp (ref "GND")
      (value "PAD.04")
      (footprint "eagle-import:PAD.04X.04")
      (libsource (lib "eagle-import") (part "PAD.04"))
    )
    (comp (ref "GND.")
      (value "PAD.04")
      (footprint "eagle-import:PAD.04X.04")
      (libsource (lib "eagle-import") (part "PAD.04"))
    )
    (comp (ref "IO-BOOT1101")
      (value "PAD.04")
      (footprint "eagle-import:PAD.04X.04")
      (libsource (lib "eagle-import") (part "PAD.04"))
    )
    (comp (ref "JP1")
      (value "FIDUCIAL1.5X3")
      (footprint "eagle-import:FIDUCIAL-1.5X3")
      (libsource (lib "eagle-import") (part "FIDUCIAL1.5X3"))
    )
    (comp (ref "JP2")
      (value "FIDUCIAL1.5X3")
      (footprint "eagle-import:FIDUCIAL-1.5X3")
      (libsource (lib "eagle-import") (part "FIDUCIAL1.5X3"))
    )
    (comp (ref "M3_MOUNT1101")
      (value "MOUNT-HOLE3.1MM")
      (footprint "eagle-import:MOUNT-HOLE3.1")
      (libsource (lib "eagle-import") (part "MOUNT-HOLE3.1MM"))
    )
    (comp (ref "M3_MOUNT1102")
      (value "MOUNT-HOLE3.1MM")
      (footprint "eagle-import:MOUNT-HOLE3.1")
      (libsource (lib "eagle-import") (part "MOUNT-HOLE3.1MM"))
    )
    (comp (ref "M3_MOUNT1103")
      (value "MOUNT-HOLE3.1MM")
      (footprint "eagle-import:MOUNT-HOLE3.1")
      (libsource (lib "eagle-import") (part "MOUNT-HOLE3.1MM"))
    )
    (comp (ref "M3_MOUNT1104")
      (value "MOUNT-HOLE3.1MM")
      (footprint "eagle-import:MOUNT-HOLE3.1")
      (libsource (lib "eagle-import") (part "MOUNT-HOLE3.1MM"))
    )
    (comp (ref "OSHW_LOGO")
      (value "OSHW-LOGOS")
      (footprint "eagle-import:OSHW-LOGO-S")
      (libsource (lib "eagle-import") (part "OSHW-LOGOS"))
    )
    (comp (ref "S1RX")
      (value "PAD.04")
      (footprint "eagle-import:PAD.04X.04")
      (libsource (lib "eagle-import") (part "PAD.04"))
    )
    (comp (ref "S1TX")
      (value "PAD.04")
      (footprint "eagle-import:PAD.04X.04")
      (libsource (lib "eagle-import") (part "PAD.04"))
    )
    (comp (ref "S2RX")
      (value "PAD.04")
      (footprint "eagle-import:PAD.04X.04")
      (libsource (lib "eagle-import") (part "PAD.04"))
    )
    (comp (ref "S2TX")
      (value "PAD.04")
      (footprint "eagle-import:PAD.04X.04")
      (libsource (lib "eagle-import") (part "PAD.04"))
    )
    (comp (ref "VDD_5V_BRICK")
      (value "PAD.04")
      (footprint "eagle-import:PAD.04X.04")
      (libsource (lib "eagle-import") (part "PAD.04"))
    )
    (comp (ref "VDD_5V_IN")
      (value "PAD.04")
      (footprint "eagle-import:PAD.04X.04")
      (libsource (lib "eagle-import") (part "PAD.04"))
    )
    (comp (ref "VDD_SERVO")
      (value "PAD.04")
      (footprint "eagle-import:PAD.04X.04")
      (libsource (lib "eagle-import") (part "PAD.04"))
    )
    (comp (ref "C401")
      (value "0u1")
      (footprint "eagle-import:0402-CAP")
      (fields (field (name "PARTNO") "CC0402ZRY5V7BB104"))
      (libsource (lib "eagle-import") (part "CAP0402"))
    )
    (comp (ref "C402")
      (value "1u")
      (footprint "eagle-import:0603-CAP")
      (fields (field (name "PARTNO") "CC0603ZRY5V7BB105"))
      (libsource (lib "eagle-import") (part "CAP0603"))
    )
    (comp (ref "C403")
      (value "5n6")
      (footprint "eagle-import:0402-CAP")
      (fields (field (name "PARTNO") "C0402C562K5RACTU"))
      (libsource (lib "eagle-import") (part "CAP0402"))
    )
    (comp (ref "C404")
      (value "0u47")
      (footprint "eagle-import:0402-CAP")
      (fields (field (name "PARTNO") "C1005X5R1C474K050BC"))
      (libsource (lib "eagle-import") (part "CAP0402"))
    )
    (comp (ref "D401")
      (value "PESD0402-140")
      (footprint "eagle-import:0402-TVS")
      (libsource (lib "eagle-import") (part "DIODE-TVS"))
    )
    (comp (ref "J401")
      (value "DF13C-2P-1.25V")
      (footprint "eagle-import:DF13C-2P-1.25V")
      (fields (field (name "PARTNO") "DF13C-2P-1.25V(20)"))
      (libsource (lib "eagle-import") (part "DF13-2P-1.25V"))
    )
    (comp (ref "J402")
      (value "DF13C-3P-1.25V")
      (footprint "eagle-import:DF13C-3P-1.25V")
      (fields (field (name "PARTNO") "DF13C-3P-1.25V(20)"))
      (libsource (lib "eagle-import") (part "DF13-3P-1.25V"))
    )
    (comp (ref "L401")
      (value "47uH")
      (footprint "eagle-import:0805-IND")
      (fields (field (name "PARTNO") "MLZ2012M470W"))
      (libsource (lib "eagle-import") (part "INDUCTOR0805"))
    )
    (comp (ref "LED401")
      (value "GREEN")
      (footprint "eagle-import:0603-LED")
      (fields (field (name "PARTNO") "APTD1608CGCK"))
      (libsource (lib "eagle-import") (part "LED0603"))
    )
    (comp (ref "LED402")
      (value "AMBER")
      (footprint "eagle-import:0603-LED")
      (fields (field (name "PARTNO") "APTD1608SECK"))
      (libsource (lib "eagle-import") (part "LED0603"))
    )
    (comp (ref "LED403")
      (value "BLUE")
      (footprint "eagle-import:0603-LED")
      (fields (field (name "PARTNO") "APTD1608QBC/D"))
      (libsource (lib "eagle-import") (part "LED0603"))
    )
    (comp (ref "R401")
      (value "9K09")
      (footprint "eagle-import:0402-RES")
      (fields (field (name "PARTNO") "RMCF0402FT9K09"))
      (libsource (lib "eagle-import") (part "RESISTOR0402-RES"))
    )
    (comp (ref "R402")
      (value "10K")
      (footprint "eagle-import:0402-RES")
      (fields (field (name "PARTNO") "RC0402FR-0710KL"))
      (libsource (lib "eagle-import") (part "RESISTOR0402-RES"))
    )
    (comp (ref "R403")
      (value "100K")
      (footprint "eagle-import:0402-RES")
      (fields (field (name "PARTNO") "RC0402FR-07100KL"))
      (libsource (lib "eagle-import") (part "RESISTOR0402-RES"))
    )
    (comp (ref "R404")
      (value "10K")
      (footprint "eagle-import:0402-RES")
      (fields (field (name "PARTNO") "RC0402FR-0710KL"))
      (libsource (lib "eagle-import") (part "RESISTOR0402-RES"))
    )
    (comp (ref "R405")
      (value "453K")
      (footprint "eagle-import:0402-RES")
      (fields (field (name "PARTNO") "RMCF0402FT453K"))
      (libsource (lib "eagle-import") (part "RESISTOR0402-RES"))
    )
    (comp (ref "R406")
      (value "16K5")
      (footprint "eagle-import:0402-RES")
      (fields (field (name "PARTNO") "RMCF0402FT16K5"))
      (libsource (lib "eagle-import") (part "RESISTOR0402-RES"))
    )
    (comp (ref "R407")
      (value "220R")
      (footprint "eagle-import:0402-RES")
      (fields (field (name "PARTNO") "RC0402FR-07220RL"))
      (libsource (lib "eagle-import") (part "RESISTOR0402-RES"))
    )
    (comp (ref "R408")
      (value "220R")
      (footprint "eagle-import:0402-RES")
      (fields (field (name "PARTNO") "RC0402FR-07220RL"))
      (libsource (lib "eagle-import") (part "RESISTOR0402-RES"))
    )
    (comp (ref "R409")
      (value "220R")
      (footprint "eagle-import:0402-RES")
      (fields (field (name "PARTNO") "RC0402FR-07220RL"))
      (libsource (lib "eagle-import") (part "RESISTOR0402-RES"))
    )
    (comp (ref "R410")
      (value "220R")
      (footprint "eagle-import:0402-RES")
      (fields (field (name "PARTNO") "RC0402FR-07220RL"))
      (libsource (lib "eagle-import") (part "RESISTOR0402-RES"))
    )
    (comp (ref "R411")
      (value "68R")
      (footprint "eagle-import:0402-RES")
      (fields (field (name "PARTNO") "ERJ-2GEJ680X"))
      (libsource (lib "eagle-import") (part "RESISTOR0402-RES"))
    )
    (comp (ref "R412")
      (value "1K5")
      (footprint "eagle-import:0402-RES")
      (fields (field (name "PARTNO") "RC0402FR-071K5L"))
      (libsource (lib "eagle-import") (part "RESISTOR0402-RES"))
    )
    (comp (ref "U401")
      (value "TCA62724FMG")
      (footprint "eagle-import:SON10")
      (libsource (lib "eagle-import") (part "TCA62724FMG"))
    )
    (comp (ref "U402")
      (value "LT3469")
      (footprint "eagle-import:SOT23-8")
      (fields (field (name "PARTNO") "LT3469ETS8"))
      (libsource (lib "eagle-import") (part "LT3469"))
    )
    (comp (ref "U403")
      (value "LRTB GFTG-T7AW-1+V7A7-29+R5T9-49-L")
      (footprint "eagle-import:6-PLCC")
      (fields (field (name "PARTNO") "LRTB GFTG-T7AW-1+V7A7-29+R5T9-49-L"))
      (libsource (lib "eagle-import") (part "RGB-LED6-PLCC"))
    )
    (comp (ref "C201")
      (value "0u1")
      (footprint "eagle-import:0402-CAP")
      (fields (field (name "PARTNO") "CC0402ZRY5V7BB104"))
      (libsource (lib "eagle-import") (part "CAP0402"))
    )
    (comp (ref "C202")
      (value "0u1")
      (footprint "eagle-import:0402-CAP")
      (fields (field (name "PARTNO") "CC0402ZRY5V7BB104"))
      (libsource (lib "eagle-import") (part "CAP0402"))
    )
    (comp (ref "D201")
      (value "PESD0402-140")
      (footprint "eagle-import:0402-TVS")
      (libsource (lib "eagle-import") (part "DIODE-TVS"))
    )
    (comp (ref "D202")
      (value "PESD0402-140")
      (footprint "eagle-import:0402-TVS")
      (libsource (lib "eagle-import") (part "DIODE-TVS"))
    )
    (comp (ref "D203")
      (value "PESD0402-140")
      (footprint "eagle-import:0402-TVS")
      (libsource (lib "eagle-import") (part "DIODE-TVS"))
    )
    (comp (ref "D204")
      (value "PESD0402-140")
      (footprint "eagle-import:0402-TVS")
      (libsource (lib "eagle-import") (part "DIODE-TVS"))
    )
    (comp (ref "J201")
      (value "DF13C-6P-1.25V")
      (footprint "eagle-import:DF13C-6P-1.25V")
      (fields (field (name "PARTNO") "DF13C-6P-1.25V(20)"))
      (libsource (lib "eagle-import") (part "DF13-6P-1.25V"))
    )
    (comp (ref "J202")
      (value "DF13C-6P-1.25V")
      (footprint "eagle-import:DF13C-6P-1.25V")
      (fields (field (name "PARTNO") "DF13C-6P-1.25V(20)"))
      (libsource (lib "eagle-import") (part "DF13-6P-1.25V"))
    )
    (comp (ref "J203")
      (value "DF13C-5P-1.25V")
      (footprint "eagle-import:DF13C-5P-1.25V")
      (fields (field (name "PARTNO") "DF13C-5P-1.25V(20)"))
      (libsource (lib "eagle-import") (part "DF13-5P-1.25V"))
    )
    (comp (ref "J204")
      (value "DF13C-3P-1.25V")
      (footprint "eagle-import:DF13C-3P-1.25V")
      (fields (field (name "PARTNO") "DF13C-3P-1.25V(20)"))
      (libsource (lib "eagle-import") (part "DF13-3P-1.25V"))
    )
    (comp (ref "J205")
      (value "DF13C-4P-1.25V")
      (footprint "eagle-import:DF13C-4P-1.25V")
      (fields (field (name "PARTNO") "DF13C-4P-1.25V(20)"))
      (libsource (lib "eagle-import") (part "DF13-4P-1.25V"))
    )
    (comp (ref "L201")
      (value "KNH16C104DA5TS")
      (footprint "eagle-import:KYOCERA-KNH16-DA")
      (libsource (lib "eagle-import") (part "KNH16C104DA5TS"))
    )
    (comp (ref "L202")
      (value "KNH16C104DA5TS")
      (footprint "eagle-import:KYOCERA-KNH16-DA")
      (libsource (lib "eagle-import") (part "KNH16C104DA5TS"))
    )
    (comp (ref "L203")
      (value "KNH16C104DA5TS")
      (footprint "eagle-import:KYOCERA-KNH16-DA")
      (libsource (lib "eagle-import") (part "KNH16C104DA5TS"))
    )
    (comp (ref "L204")
      (value "KNH16C104DA5TS")
      (footprint "eagle-import:KYOCERA-KNH16-DA")
      (libsource (lib "eagle-import") (part "KNH16C104DA5TS"))
    )
    (comp (ref "R201")
      (value "120R")
      (footprint "eagle-import:0402-RES")
      (fields (field (name "PARTNO") "RC0402FR-07120RL"))
      (libsource (lib "eagle-import") (part "RESISTOR0402-RES"))
    )
    (comp (ref "R202")
      (value "120R")
      (footprint "eagle-import:0402-RES")
      (fields (field (name "PARTNO") "RC0402FR-07120RL"))
      (libsource (lib "eagle-import") (part "RESISTOR0402-RES"))
    )
    (comp (ref "R203")
      (value "120R")
      (footprint "eagle-import:0402-RES")
      (fields (field (name "PARTNO") "RC0402FR-07120RL"))
      (libsource (lib "eagle-import") (part "RESISTOR0402-RES"))
    )
    (comp (ref "R204")
      (value "120R")
      (footprint "eagle-import:0402-RES")
      (fields (field (name "PARTNO") "RC0402FR-07120RL"))
      (libsource (lib "eagle-import") (part "RESISTOR0402-RES"))
    )
    (comp (ref "R205")
      (value "120R")
      (footprint "eagle-import:0402-RES")
      (fields (field (name "PARTNO") "RC0402FR-07120RL"))
      (libsource (lib "eagle-import") (part "RESISTOR0402-RES"))
    )
    (comp (ref "R206")
      (value "120R")
      (footprint "eagle-import:0402-RES")
      (fields (field (name "PARTNO") "RC0402FR-07120RL"))
      (libsource (lib "eagle-import") (part "RESISTOR0402-RES"))
    )
    (comp (ref "R207")
      (value "10K/0.1%")
      (footprint "eagle-import:0402-RES")
      (fields (field (name "PARTNO") "ERA-2AEB103X"))
      (libsource (lib "eagle-import") (part "RESISTOR0402-RES"))
    )
    (comp (ref "R208")
      (value "10K/0.1%")
      (footprint "eagle-import:0402-RES")
      (fields (field (name "PARTNO") "ERA-2AEB103X"))
      (libsource (lib "eagle-import") (part "RESISTOR0402-RES"))
    )
    (comp (ref "R209")
      (value "10K/0.1%")
      (footprint "eagle-import:0402-RES")
      (fields (field (name "PARTNO") "ERA-2AEB103X"))
      (libsource (lib "eagle-import") (part "RESISTOR0402-RES"))
    )
    (comp (ref "R210")
      (value "10K/0.1%")
      (footprint "eagle-import:0402-RES")
      (fields (field (name "PARTNO") "ERA-2AEB103X"))
      (libsource (lib "eagle-import") (part "RESISTOR0402-RES"))
    )
    (comp (ref "R211")
      (value "120R")
      (footprint "eagle-import:0402-RES")
      (fields (field (name "PARTNO") "RC0402FR-07120RL"))
      (libsource (lib "eagle-import") (part "RESISTOR0402-RES"))
    )
    (comp (ref "R212")
      (value "120R")
      (footprint "eagle-import:0402-RES")
      (fields (field (name "PARTNO") "RC0402FR-07120RL"))
      (libsource (lib "eagle-import") (part "RESISTOR0402-RES"))
    )
    (comp (ref "U201")
      (value "TXS0108QFN20")
      (footprint "eagle-import:QFN20-RGY")
      (fields (field (name "PARTNO") "TXS0108ERGYR"))
      (libsource (lib "eagle-import") (part "TXS0108QFN20"))
    )
  )
  (nets
    (net (code "1") (name "ACCEL_DRDY") (class "Default")
      (node (ref "U101") (pin "P$11") (pinfunction "GPIO17_P$11") (pintype "bidirectional"))
      (node (ref "U304") (pin "11") (pinfunction "INT1_11") (pintype "bidirectional"))
    )
    (net (code "2") (name "ALARM") (class "Default")
      (node (ref "R401") (pin "P$2") (pinfunction "2_P$2") (pintype "passive"))
      (node (ref "U101") (pin "P$12") (pinfunction "GPIO18_P$12") (pintype "bidirectional"))
    )
    (net (code "3") (name "BATT_CURRENT_SENS") (class "Default")
      (node (ref "R702") (pin "P$1") (pinfunction "1_P$1") (pintype "passive"))
      (node (ref "U501") (pin "9") (pinfunction "PC1_9") (pintype "bidirectional"))
    )
    (net (code "4") (name "BATT_VOLTAGE_SENS") (class "Default")
      (node (ref "R701") (pin "P$1") (pinfunction "1_P$1") (pintype "passive"))
      (node (ref "U501") (pin "8") (pinfunction "PC0_8") (pintype "bidirectional"))
    )
    (net (code "5") (name "GND") (class "Default")
      (node (ref "C101") (pin "P$2") (pinfunction "2_P$2") (pintype "passive"))
      (node (ref "C201") (pin "P$2") (pinfunction "2_P$2") (pintype "passive"))
      (node (ref "C202") (pin "P$2") (pinfunction "2_P$2") (pintype "passive"))
      (node (ref "C301") (pin "P$2") (pinfunction "2_P$2") (pintype "passive"))
      (node (ref "C302") (pin "P$2") (pinfunction "2_P$2") (pintype "passive"))
      (node (ref "C303") (pin "P$2") (pinfunction "2_P$2") (pintype "passive"))
      (node (ref "C304") (pin "P$2") (pinfunction "2_P$2") (pintype "passive"))
      (node (ref "C305") (pin "P$2") (pinfunction "2_P$2") (pintype "passive"))
      (node (ref "C306") (pin "P$2") (pinfunction "2_P$2") (pintype "passive"))
      (node (ref "C307") (pin "P$2") (pinfunction "2_P$2") (pintype "passive"))
      (node (ref "C308") (pin "P$2") (pinfunction "2_P$2") (pintype "passive"))
      (node (ref "C309") (pin "P$2") (pinfunction "2_P$2") (pintype "passive"))
      (node (ref "C311") (pin "P$2") (pinfunction "2_P$2") (pintype "passive"))
      (node (ref "C312") (pin "P$2") (pinfunction "2_P$2") (pintype "passive"))
      (node (ref "C313") (pin "P$2") (pinfunction "2_P$2") (pintype "passive"))
      (node (ref "C314") (pin "P$2") (pinfunction "2_P$2") (pintype "passive"))
      (node (ref "C315") (pin "P$2") (pinfunction "2_P$2") (pintype "passive"))
      (node (ref "C401") (pin "P$2") (pinfunction "2_P$2") (pintype "passive"))
      (node (ref "C402") (pin "P$2") (pinfunction "2_P$2") (pintype "passive"))
      (node (ref "C403") (pin "P$2") (pinfunction "2_P$2") (pintype "passive"))
      (node (ref "C404") (pin "P$2") (pinfunction "2_P$2") (pintype "passive"))
      (node (ref "C501") (pin "P$1") (pinfunction "1_P$1") (pintype "passive"))
      (node (ref "C502") (pin "P$2") (pinfunction "2_P$2") (pintype "passive"))
      (node (ref "C503") (pin "P$2") (pinfunction "2_P$2") (pintype "passive"))
      (node (ref "C504") (pin "P$2") (pinfunction "2_P$2") (pintype "passive"))
      (node (ref "C505") (pin "P$2") (pinfunction "2_P$2") (pintype "passive"))
      (node (ref "C506") (pin "P$1") (pinfunction "1_P$1") (pintype "passive"))
      (node (ref "C507") (pin "P$2") (pinfunction "2_P$2") (pintype "passive"))
      (node (ref "C601") (pin "P$2") (pinfunction "2_P$2") (pintype "passive"))
      (node (ref "C701") (pin "P$2") (pinfunction "2_P$2") (pintype "passive"))
      (node (ref "C702") (pin "P$2") (pinfunction "2_P$2") (pintype "passive"))
      (node (ref "C703") (pin "P$2") (pinfunction "2_P$2") (pintype "passive"))
      (node (ref "C704") (pin "P$2") (pinfunction "2_P$2") (pintype "passive"))
      (node (ref "C705") (pin "P$2") (pinfunction "2_P$2") (pintype "passive"))
      (node (ref "C706") (pin "P$2") (pinfunction "2_P$2") (pintype "passive"))
      (node (ref "C707") (pin "P$2") (pinfunction "2_P$2") (pintype "passive"))
      (node (ref "D201") (pin "A") (pinfunction "A_A") (pintype "passive"))
      (node (ref "D202") (pin "A") (pinfunction "A_A") (pintype "passive"))
      (node (ref "D203") (pin "A") (pinfunction "A_A") (pintype "passive"))
      (node (ref "D204") (pin "A") (pinfunction "A_A") (pintype "passive"))
      (node (ref "D401") (pin "A") (pinfunction "A_A") (pintype "passive"))
      (node (ref "D501") (pin "A") (pinfunction "A_A") (pintype "passive"))
      (node (ref "D601") (pin "A") (pinfunction "A_A") (pintype "passive"))
      (node (ref "D602") (pin "A") (pinfunction "A_A") (pintype "passive"))
      (node (ref "D703") (pin "A") (pinfunction "A_A") (pintype "passive"))
      (node (ref "D704") (pin "A") (pinfunction "A_A") (pintype "passive"))
      (node (ref "GND") (pin "P$1") (pinfunction "P$1_P$1") (pintype "passive"))
      (node (ref "GND.") (pin "P$1") (pinfunction "P$1_P$1") (pintype "passive"))
      (node (ref "J201") (pin "6") (pinfunction "6_6") (pintype "passive"))
      (node (ref "J202") (pin "6") (pinfunction "6_6") (pintype "passive"))
      (node (ref "J203") (pin "3") (pinfunction "3_3") (pintype "passive"))
      (node (ref "J203") (pin "5") (pinfunction "5_5") (pintype "passive"))
      (node (ref "J204") (pin "3") (pinfunction "3_3") (pintype "passive"))
      (node (ref "J205") (pin "4") (pinfunction "4_4") (pintype "passive"))
      (node (ref "J401") (pin "2") (pinfunction "2_2") (pintype "passive"))
      (node (ref "J501") (pin "P$2") (pinfunction "P$2_P$2") (pintype "bidirectional"))
      (node (ref "J601") (pin "12") (pinfunction "S_12") (pintype "passive"))
      (node (ref "J601") (pin "15") (pinfunction "S_15") (pintype "passive"))
      (node (ref "J601") (pin "18") (pinfunction "S_18") (pintype "passive"))
      (node (ref "J601") (pin "21") (pinfunction "S_21") (pintype "passive"))
      (node (ref "J601") (pin "24") (pinfunction "S_24") (pintype "passive"))
      (node (ref "J601") (pin "27") (pinfunction "S_27") (pintype "passive"))
      (node (ref "J601") (pin "3") (pinfunction "S_3") (pintype "passive"))
      (node (ref "J601") (pin "30") (pinfunction "S_30") (pintype "passive"))
      (node (ref "J601") (pin "6") (pinfunction "S_6") (pintype "passive"))
      (node (ref "J601") (pin "9") (pinfunction "S_9") (pintype "passive"))
      (node (ref "J701") (pin "5") (pinfunction "5_5") (pintype "passive"))
      (node (ref "J701") (pin "6") (pinfunction "6_6") (pintype "passive"))
      (node (ref "JX501") (pin "3") (pinfunction "GND_3") (pintype "bidirectional"))
      (node (ref "JX502") (pin "3") (pinfunction "S_3") (pintype "passive"))
      (node (ref "JX502") (pin "5") (pinfunction "S_5") (pintype "passive"))
      (node (ref "JX502") (pin "9") (pinfunction "S_9") (pintype "passive"))
      (node (ref "L201") (pin "P$3") (pinfunction "P$3_P$3") (pintype "bidirectional"))
      (node (ref "L201") (pin "P$4") (pinfunction "P$3_P$4") (pintype "bidirectional"))
      (node (ref "L201") (pin "P$5") (pinfunction "P$3_P$5") (pintype "bidirectional"))
      (node (ref "L202") (pin "P$3") (pinfunction "P$3_P$3") (pintype "bidirectional"))
      (node (ref "L202") (pin "P$4") (pinfunction "P$3_P$4") (pintype "bidirectional"))
      (node (ref "L202") (pin "P$5") (pinfunction "P$3_P$5") (pintype "bidirectional"))
      (node (ref "L203") (pin "P$3") (pinfunction "P$3_P$3") (pintype "bidirectional"))
      (node (ref "L203") (pin "P$4") (pinfunction "P$3_P$4") (pintype "bidirectional"))
      (node (ref "L203") (pin "P$5") (pinfunction "P$3_P$5") (pintype "bidirectional"))
      (node (ref "L204") (pin "P$3") (pinfunction "P$3_P$3") (pintype "bidirectional"))
      (node (ref "L204") (pin "P$4") (pinfunction "P$3_P$4") (pintype "bidirectional"))
      (node (ref "L204") (pin "P$5") (pinfunction "P$3_P$5") (pintype "bidirectional"))
      (node (ref "L701") (pin "P$3") (pinfunction "P$3_P$3") (pintype "bidirectional"))
      (node (ref "L701") (pin "P$4") (pinfunction "P$3_P$4") (pintype "bidirectional"))
      (node (ref "L701") (pin "P$5") (pinfunction "P$3_P$5") (pintype "bidirectional"))
      (node (ref "L702") (pin "P$3") (pinfunction "P$3_P$3") (pintype "bidirectional"))
      (node (ref "L702") (pin "P$4") (pinfunction "P$3_P$4") (pintype "bidirectional"))
      (node (ref "L702") (pin "P$5") (pinfunction "P$3_P$5") (pintype "bidirectional"))
      (node (ref "R210") (pin "P$1") (pinfunction "1_P$1") (pintype "passive"))
      (node (ref "R402") (pin "P$2") (pinfunction "2_P$2") (pintype "passive"))
      (node (ref "R404") (pin "P$1") (pinfunction "1_P$1") (pintype "passive"))
      (node (ref "R406") (pin "P$2") (pinfunction "2_P$2") (pintype "passive"))
      (node (ref "R407") (pin "P$1") (pinfunction "1_P$1") (pintype "passive"))
      (node (ref "R412") (pin "P$2") (pinfunction "2_P$2") (pintype "passive"))
      (node (ref "R501") (pin "P$2") (pinfunction "2_P$2") (pintype "passive"))
      (node (ref "R502") (pin "P$2") (pinfunction "2_P$2") (pintype "passive"))
      (node (ref "R606") (pin "P$1") (pinfunction "1_P$1") (pintype "passive"))
      (node (ref "R703") (pin "P$2") (pinfunction "2_P$2") (pintype "passive"))
      (node (ref "R704") (pin "P$2") (pinfunction "2_P$2") (pintype "passive"))
      (node (ref "R706") (pin "P$2") (pinfunction "2_P$2") (pintype "passive"))
      (node (ref "S501") (pin "B3") (pinfunction "2_B3") (pintype "passive"))
      (node (ref "U101") (pin "P$14") (pinfunction "GND_P$14") (pintype "bidirectional"))
      (node (ref "U101") (pin "P$20") (pinfunction "GND_P$20") (pintype "bidirectional"))
      (node (ref "U101") (pin "P$25") (pinfunction "GND_P$25") (pintype "bidirectional"))
      (node (ref "U101") (pin "P$30") (pinfunction "GND_P$30") (pintype "bidirectional"))
      (node (ref "U101") (pin "P$34") (pinfunction "GND_P$34") (pintype "bidirectional"))
      (node (ref "U101") (pin "P$39") (pinfunction "GND_P$39") (pintype "bidirectional"))
      (node (ref "U101") (pin "P$6") (pinfunction "GND_P$6") (pintype "bidirectional"))
      (node (ref "U101") (pin "P$9") (pinfunction "GND_P$9") (pintype "bidirectional"))
      (node (ref "U102") (pin "4") (pinfunction "VSS_4") (pintype "bidirectional"))
      (node (ref "U201") (pin "11") (pinfunction "GND_11") (pintype "power_in"))
      (node (ref "U301") (pin "10") (pinfunction "RES_P10_GND_10") (pintype "bidirectional"))
      (node (ref "U301") (pin "11") (pinfunction "RES_P11_GND_11") (pintype "bidirectional"))
      (node (ref "U301") (pin "12") (pinfunction "RES_P12_GND_12") (pintype "bidirectional"))
      (node (ref "U301") (pin "13") (pinfunction "GND_13") (pintype "bidirectional"))
      (node (ref "U301") (pin "8") (pinfunction "RES_P8_GND_8") (pintype "bidirectional"))
      (node (ref "U301") (pin "9") (pinfunction "RES_P9_GND_9") (pintype "bidirectional"))
      (node (ref "U302") (pin "10") (pinfunction "GND_10") (pintype "bidirectional"))
      (node (ref "U302") (pin "11") (pinfunction "GND_11") (pintype "bidirectional"))
      (node (ref "U302") (pin "12") (pinfunction "GND_12") (pintype "bidirectional"))
      (node (ref "U302") (pin "13") (pinfunction "GND_13") (pintype "bidirectional"))
      (node (ref "U302") (pin "9") (pinfunction "GND_9") (pintype "bidirectional"))
      (node (ref "U304") (pin "10") (pinfunction "RSRV_10") (pintype "bidirectional"))
      (node (ref "U304") (pin "12") (pinfunction "GND_12") (pintype "bidirectional"))
      (node (ref "U304") (pin "13") (pinfunction "GND_13") (pintype "bidirectional"))
      (node (ref "U304") (pin "16") (pinfunction "GND_16") (pintype "bidirectional"))
      (node (ref "U304") (pin "5") (pinfunction "GND_5") (pintype "bidirectional"))
      (node (ref "U305") (pin "1") (pinfunction "CLKIN_1") (pintype "bidirectional"))
      (node (ref "U305") (pin "18") (pinfunction "GND_18") (pintype "bidirectional"))
      (node (ref "U306") (pin "2") (pinfunction "PS_2") (pintype "bidirectional"))
      (node (ref "U306") (pin "3") (pinfunction "GND_3") (pintype "bidirectional"))
      (node (ref "U401") (pin "5") (pinfunction "GND_5") (pintype "power_in"))
      (node (ref "U402") (pin "4") (pinfunction "GND_4") (pintype "power_in"))
      (node (ref "U501") (pin "12") (pinfunction "VSSA_12") (pintype "power_in"))
      (node (ref "U501") (pin "18") (pinfunction "VSS_18") (pintype "power_in"))
      (node (ref "U501") (pin "31") (pinfunction "VSS_31") (pintype "power_in"))
      (node (ref "U501") (pin "47") (pinfunction "VSS_47") (pintype "power_in"))
      (node (ref "U501") (pin "63") (pinfunction "VSS_63") (pintype "power_in"))
      (node (ref "U601") (pin "1") (pinfunction "~{1OE}_1") (pintype "input"))
      (node (ref "U601") (pin "4") (pinfunction "GND_4") (pintype "power_in"))
      (node (ref "U701") (pin "2") (pinfunction "GND_2") (pintype "bidirectional"))
      (node (ref "U701") (pin "GND") (pinfunction "GND_GND") (pintype "bidirectional"))
      (node (ref "X501") (pin "2") (pinfunction "NC_2_2") (pintype "power_in"))
      (node (ref "X501") (pin "4") (pinfunction "NC_4_4") (pintype "power_in"))
    )
    (net (code "6") (name "GYRO_DRDY") (class "Default")
      (node (ref "U101") (pin "P$31") (pinfunction "GPIO6_P$31") (pintype "bidirectional"))
      (node (ref "U301") (pin "6") (pinfunction "DRDY/INT2_6") (pintype "output"))
      (node (ref "U302") (pin "6") (pinfunction "DRDY/INT2_6") (pintype "bidirectional"))
    )
    (net (code "7") (name "IO-BOOT0") (class "Default")
      (node (ref "IO-BOOT1101") (pin "P$1") (pinfunction "P$1_P$1") (pintype "passive"))
      (node (ref "R501") (pin "P$1") (pinfunction "1_P$1") (pintype "passive"))
      (node (ref "U501") (pin "60") (pinfunction "BOOT0_60") (pintype "input"))
    )
    (net (code "8") (name "IO-CAN_RX") (class "Default")
      (node (ref "CAN_L") (pin "P$1") (pinfunction "P$1_P$1") (pintype "passive"))
      (node (ref "R206") (pin "P$1") (pinfunction "1_P$1") (pintype "passive"))
      (node (ref "U501") (pin "61") (pinfunction "PB8_61") (pintype "bidirectional"))
    )
    (net (code "9") (name "IO-CAN_TX") (class "Default")
      (node (ref "CAN_H") (pin "P$1") (pinfunction "P$1_P$1") (pintype "passive"))
      (node (ref "R205") (pin "P$1") (pinfunction "1_P$1") (pintype "passive"))
      (node (ref "U501") (pin "62") (pinfunction "PB9_62") (pintype "bidirectional"))
    )
    (net (code "10") (name "IO-CH1") (class "Default")
      (node (ref "J601") (pin "28") (pinfunction "S_28") (pintype "passive"))
      (node (ref "U501") (pin "14") (pinfunction "PA0_14") (pintype "bidirectional"))
    )
    (net (code "11") (name "IO-CH2") (class "Default")
      (node (ref "J601") (pin "25") (pinfunction "S_25") (pintype "passive"))
      (node (ref "U501") (pin "15") (pinfunction "PA1_15") (pintype "bidirectional"))
    )
    (net (code "12") (name "IO-CH3") (class "Default")
      (node (ref "J601") (pin "22") (pinfunction "S_22") (pintype "passive"))
      (node (ref "U501") (pin "58") (pinfunction "PB6_58") (pintype "bidirectional"))
    )
    (net (code "13") (name "IO-CH4") (class "Default")
      (node (ref "J601") (pin "19") (pinfunction "S_19") (pintype "passive"))
      (node (ref "U501") (pin "59") (pinfunction "PB7_59") (pintype "bidirectional"))
    )
    (net (code "14") (name "IO-CH5") (class "Default")
      (node (ref "J601") (pin "16") (pinfunction "S_16") (pintype "passive"))
      (node (ref "U501") (pin "22") (pinfunction "PA6_22") (pintype "bidirectional"))
    )
    (net (code "15") (name "IO-CH6") (class "Default")
      (node (ref "J601") (pin "13") (pinfunction "S_13") (pintype "passive"))
      (node (ref "U501") (pin "23") (pinfunction "PA7_23") (pintype "bidirectional"))
    )
    (net (code "16") (name "IO-CH7") (class "Default")
      (node (ref "J601") (pin "10") (pinfunction "S_10") (pintype "passive"))
      (node (ref "U501") (pin "26") (pinfunction "PB0_26") (pintype "bidirectional"))
    )
    (net (code "17") (name "IO-CH8") (class "Default")
      (node (ref "J601") (pin "7") (pinfunction "S_7") (pintype "passive"))
      (node (ref "U501") (pin "27") (pinfunction "PB1_27") (pintype "bidirectional"))
    )
    (net (code "18") (name "IO-RPI-SPI_MISO") (class "Default")
      (node (ref "U101") (pin "P$21") (pinfunction "GPIO9_P$21") (pintype "bidirectional"))
      (node (ref "U102") (pin "2") (pinfunction "Q_2") (pintype "bidirectional"))
      (node (ref "U301") (pin "4") (pinfunction "SDO/SA0_4") (pintype "bidirectional"))
      (node (ref "U302") (pin "4") (pinfunction "SDO/SA0_4") (pintype "bidirectional"))
      (node (ref "U304") (pin "7") (pinfunction "SDO/SA0_7") (pintype "bidirectional"))
      (node (ref "U305") (pin "9") (pinfunction "AD0/SDO_9") (pintype "bidirectional"))
      (node (ref "U306") (pin "6") (pinfunction "SDO_6") (pintype "bidirectional"))
      (node (ref "U501") (pin "56") (pinfunction "PB4_56") (pintype "bidirectional"))
    )
    (net (code "19") (name "IO-RPI-SPI_MOSI") (class "Default")
      (node (ref "U101") (pin "P$19") (pinfunction "GPIO10_P$19") (pintype "bidirectional"))
      (node (ref "U102") (pin "5") (pinfunction "D_5") (pintype "bidirectional"))
      (node (ref "U301") (pin "3") (pinfunction "SDA/SDI/SDO_3") (pintype "bidirectional"))
      (node (ref "U302") (pin "3") (pinfunction "SDA/SDI/SDO_3") (pintype "bidirectional"))
      (node (ref "U304") (pin "6") (pinfunction "SDA/SDI/SDO_6") (pintype "bidirectional"))
      (node (ref "U305") (pin "24") (pinfunction "SDA/SDI_24") (pintype "bidirectional"))
      (node (ref "U306") (pin "7") (pinfunction "SDI/SDA_7") (pintype "bidirectional"))
      (node (ref "U501") (pin "57") (pinfunction "PB5_57") (pintype "bidirectional"))
    )
    (net (code "20") (name "IO-RPI-SPI_NSS") (class "Default")
      (node (ref "U101") (pin "P$26") (pinfunction "GPIO7_P$26") (pintype "bidirectional"))
      (node (ref "U501") (pin "50") (pinfunction "PA15_50") (pintype "bidirectional"))
    )
    (net (code "21") (name "IO-RPI-SPI_SCK") (class "Default")
      (node (ref "JX502") (pin "6") (pinfunction "S_6") (pintype "passive"))
      (node (ref "U101") (pin "P$23") (pinfunction "GPIO11_P$23") (pintype "bidirectional"))
      (node (ref "U102") (pin "6") (pinfunction "C_6") (pintype "bidirectional"))
      (node (ref "U301") (pin "2") (pinfunction "SCL/SPC_2") (pintype "input"))
      (node (ref "U302") (pin "2") (pinfunction "SCL/SPC_2") (pintype "bidirectional"))
      (node (ref "U304") (pin "4") (pinfunction "SCL/SPC_4") (pintype "bidirectional"))
      (node (ref "U305") (pin "23") (pinfunction "SCL/SCLK_23") (pintype "bidirectional"))
      (node (ref "U306") (pin "8") (pinfunction "SCLK_8") (pintype "bidirectional"))
      (node (ref "U501") (pin "55") (pinfunction "PB3_55") (pintype "bidirectional"))
    )
    (net (code "22") (name "IO-SWCLK") (class "Default")
      (node (ref "JX502") (pin "4") (pinfunction "S_4") (pintype "passive"))
      (node (ref "U501") (pin "49") (pinfunction "PA14_49") (pintype "bidirectional"))
    )
    (net (code "23") (name "IO-SWDIO") (class "Default")
      (node (ref "JX502") (pin "2") (pinfunction "S_2") (pintype "passive"))
      (node (ref "U501") (pin "46") (pinfunction "PA13_46") (pintype "bidirectional"))
    )
    (net (code "24") (name "IO-USART1_RX") (class "Default")
      (node (ref "J501") (pin "P$3") (pinfunction "P$3_P$3") (pintype "bidirectional"))
      (node (ref "JX501") (pin "2") (pinfunction "+5V_2") (pintype "bidirectional"))
      (node (ref "U501") (pin "43") (pinfunction "PA10_43") (pintype "bidirectional"))
    )
    (net (code "25") (name "IO-USART1_TX") (class "Default")
      (node (ref "JX501") (pin "1") (pinfunction "PPM_1") (pintype "bidirectional"))
      (node (ref "U501") (pin "42") (pinfunction "PA9_42") (pintype "bidirectional"))
    )
    (net (code "26") (name "IO-USART2_RX") (class "Default")
      (node (ref "U201") (pin "1") (pinfunction "A1_1") (pintype "bidirectional"))
      (node (ref "U501") (pin "17") (pinfunction "PA3_17") (pintype "bidirectional"))
    )
    (net (code "27") (name "IO-USART2_TX") (class "Default")
      (node (ref "U201") (pin "3") (pinfunction "A2_3") (pintype "bidirectional"))
      (node (ref "U501") (pin "16") (pinfunction "PA2_16") (pintype "bidirectional"))
    )
    (net (code "28") (name "IO-VDD_3V3") (class "Default")
      (node (ref "C101") (pin "P$1") (pinfunction "1_P$1") (pintype "passive"))
      (node (ref "C201") (pin "P$1") (pinfunction "1_P$1") (pintype "passive"))
      (node (ref "C401") (pin "P$1") (pinfunction "1_P$1") (pintype "passive"))
      (node (ref "C502") (pin "P$1") (pinfunction "1_P$1") (pintype "passive"))
      (node (ref "C503") (pin "P$1") (pinfunction "1_P$1") (pintype "passive"))
      (node (ref "C504") (pin "P$1") (pinfunction "1_P$1") (pintype "passive"))
      (node (ref "C507") (pin "P$1") (pinfunction "1_P$1") (pintype "passive"))
      (node (ref "C601") (pin "P$1") (pinfunction "1_P$1") (pintype "passive"))
      (node (ref "C706") (pin "P$1") (pinfunction "1_P$1") (pintype "passive"))
      (node (ref "C707") (pin "P$1") (pinfunction "1_P$1") (pintype "passive"))
      (node (ref "D401") (pin "C") (pinfunction "C_C") (pintype "passive"))
      (node (ref "D501") (pin "C") (pinfunction "C_C") (pintype "passive"))
      (node (ref "J402") (pin "1") (pinfunction "1_1") (pintype "passive"))
      (node (ref "J501") (pin "P$1") (pinfunction "P$1_P$1") (pintype "bidirectional"))
      (node (ref "JX502") (pin "1") (pinfunction "S_1") (pintype "passive"))
      (node (ref "U102") (pin "3") (pinfunction "~{W}_3") (pintype "bidirectional"))
      (node (ref "U102") (pin "7") (pinfunction "~{HOLD}_7") (pintype "bidirectional"))
      (node (ref "U102") (pin "8") (pinfunction "VDD_8") (pintype "bidirectional"))
      (node (ref "U201") (pin "10") (pinfunction "OE_10") (pintype "input"))
      (node (ref "U201") (pin "19") (pinfunction "VCCB_19") (pintype "input"))
      (node (ref "U201") (pin "2") (pinfunction "VCCA_2") (pintype "input"))
      (node (ref "U401") (pin "1") (pinfunction "~{SHDN}_1") (pintype "input"))
      (node (ref "U401") (pin "10") (pinfunction "VIN_10") (pintype "power_in"))
      (node (ref "U501") (pin "1") (pinfunction "VBAT_1") (pintype "power_in"))
      (node (ref "U501") (pin "13") (pinfunction "VDDA_13") (pintype "power_in"))
      (node (ref "U501") (pin "19") (pinfunction "VDD_19") (pintype "power_in"))
      (node (ref "U501") (pin "32") (pinfunction "VDD_32") (pintype "power_in"))
      (node (ref "U501") (pin "48") (pinfunction "VDD_48") (pintype "power_in"))
      (node (ref "U501") (pin "64") (pinfunction "VDD_64") (pintype "power_in"))
      (node (ref "U601") (pin "8") (pinfunction "VCC_8") (pintype "power_in"))
      (node (ref "U701") (pin "8") (pinfunction "VOUT1_8") (pintype "bidirectional"))
    )
    (net (code "29") (name "IO-~{RESET}") (class "Default")
      (node (ref "C501") (pin "P$2") (pinfunction "2_P$2") (pintype "passive"))
      (node (ref "S501") (pin "A1") (pinfunction "1_A1") (pintype "passive"))
      (node (ref "U501") (pin "7") (pinfunction "NRST_7") (pintype "input"))
      (node (ref "U701") (pin "3") (pinfunction "POR2_3") (pintype "bidirectional"))
    )
    (net (code "30") (name "IO_AUX_ADC1") (class "Default")
      (node (ref "R208") (pin "P$1") (pinfunction "1_P$1") (pintype "passive"))
      (node (ref "U501") (pin "24") (pinfunction "PC4_24") (pintype "bidirectional"))
    )
    (net (code "31") (name "IO_AUX_ADC2") (class "Default")
      (node (ref "R207") (pin "P$1") (pinfunction "1_P$1") (pintype "passive"))
      (node (ref "U501") (pin "25") (pinfunction "PC5_25") (pintype "bidirectional"))
    )
    (net (code "32") (name "LED-~{RESET}") (class "Default")
      (node (ref "U101") (pin "P$7") (pinfunction "GPIO4_P$7") (pintype "bidirectional"))
      (node (ref "U401") (pin "4") (pinfunction "~{RESET}_4") (pintype "input"))
    )
    (net (code "33") (name "MAG_DRDY") (class "Default")
      (node (ref "U101") (pin "P$13") (pinfunction "GPIO27_P$13") (pintype "bidirectional"))
      (node (ref "U304") (pin "9") (pinfunction "INT2_9") (pintype "bidirectional"))
    )
    (net (code "34") (name "MPU_DRDY") (class "Default")
      (node (ref "U101") (pin "P$18") (pinfunction "GPIO24_P$18") (pintype "bidirectional"))
      (node (ref "U305") (pin "12") (pinfunction "INT_12") (pintype "bidirectional"))
    )
    (net (code "35") (name "Net-(C304-1)") (class "Default")
      (node (ref "C304") (pin "P$1") (pinfunction "1_P$1") (pintype "passive"))
      (node (ref "U301") (pin "14") (pinfunction "PLLFILT_14") (pintype "bidirectional"))
    )
    (net (code "36") (name "Net-(C305-1)") (class "Default")
      (node (ref "C305") (pin "P$1") (pinfunction "1_P$1") (pintype "passive"))
      (node (ref "U302") (pin "14") (pinfunction "CAP_14") (pintype "bidirectional"))
    )
    (net (code "37") (name "Net-(C309-1)") (class "Default")
      (node (ref "C309") (pin "P$1") (pinfunction "1_P$1") (pintype "passive"))
      (node (ref "U304") (pin "15") (pinfunction "C1_15") (pintype "bidirectional"))
    )
    (net (code "38") (name "Net-(C310-1)") (class "Default")
      (node (ref "C310") (pin "P$1") (pinfunction "1_P$1") (pintype "passive"))
      (node (ref "U304") (pin "2") (pinfunction "SETC_2") (pintype "bidirectional"))
    )
    (net (code "39") (name "Net-(C310-2)") (class "Default")
      (node (ref "C310") (pin "P$2") (pinfunction "2_P$2") (pintype "passive"))
      (node (ref "U304") (pin "3") (pinfunction "SETP_3") (pintype "bidirectional"))
    )
    (net (code "40") (name "Net-(C312-1)") (class "Default")
      (node (ref "C312") (pin "P$1") (pinfunction "1_P$1") (pintype "passive"))
      (node (ref "U305") (pin "10") (pinfunction "REGOUT_10") (pintype "bidirectional"))
    )
    (net (code "41") (name "Net-(C315-1)") (class "Default")
      (node (ref "C315") (pin "P$1") (pinfunction "1_P$1") (pintype "passive"))
      (node (ref "U305") (pin "20") (pinfunction "CPOUT_20") (pintype "bidirectional"))
    )
    (net (code "42") (name "Net-(C403-1)") (class "Default")
      (node (ref "C403") (pin "P$1") (pinfunction "1_P$1") (pintype "passive"))
      (node (ref "J401") (pin "1") (pinfunction "1_1") (pintype "passive"))
      (node (ref "R403") (pin "P$1") (pinfunction "1_P$1") (pintype "passive"))
      (node (ref "U402") (pin "1") (pinfunction "OUT_1") (pintype "output"))
    )
    (net (code "43") (name "Net-(C404-1)") (class "Default")
      (node (ref "C404") (pin "P$1") (pinfunction "1_P$1") (pintype "passive"))
      (node (ref "R405") (pin "P$1") (pinfunction "1_P$1") (pintype "passive"))
      (node (ref "U402") (pin "6") (pinfunction "VCC_6") (pintype "bidirectional"))
    )
    (net (code "44") (name "Net-(C505-1)") (class "Default")
      (node (ref "C505") (pin "P$1") (pinfunction "1_P$1") (pintype "passive"))
      (node (ref "U501") (pin "5") (pinfunction "PH0/OSC<=_5") (pintype "bidirectional"))
      (node (ref "X501") (pin "3") (pinfunction "3_3") (pintype "bidirectional"))
    )
    (net (code "45") (name "Net-(C506-2)") (class "Default")
      (node (ref "C506") (pin "P$2") (pinfunction "2_P$2") (pintype "passive"))
      (node (ref "U501") (pin "6") (pinfunction "PH1/OSC=>_6") (pintype "bidirectional"))
      (node (ref "X501") (pin "1") (pinfunction "1_1") (pintype "bidirectional"))
    )
    (net (code "46") (name "Net-(C702-1)") (class "Default")
      (node (ref "C702") (pin "P$1") (pinfunction "1_P$1") (pintype "passive"))
      (node (ref "U701") (pin "6") (pinfunction "CSET_6") (pintype "bidirectional"))
    )
    (net (code "47") (name "Net-(D201-PadC)") (class "Default")
      (node (ref "D201") (pin "C") (pinfunction "C_C") (pintype "passive"))
      (node (ref "J201") (pin "1") (pinfunction "1_1") (pintype "passive"))
      (node (ref "L201") (pin "P$2") (pinfunction "P$2_P$2") (pintype "bidirectional"))
    )
    (net (code "48") (name "Net-(D202-PadC)") (class "Default")
      (node (ref "D202") (pin "C") (pinfunction "C_C") (pintype "passive"))
      (node (ref "J202") (pin "1") (pinfunction "1_1") (pintype "passive"))
      (node (ref "L202") (pin "P$2") (pinfunction "P$2_P$2") (pintype "bidirectional"))
    )
    (net (code "49") (name "Net-(D203-PadC)") (class "Default")
      (node (ref "D203") (pin "C") (pinfunction "C_C") (pintype "passive"))
      (node (ref "J203") (pin "1") (pinfunction "1_1") (pintype "passive"))
      (node (ref "L203") (pin "P$2") (pinfunction "P$2_P$2") (pintype "bidirectional"))
    )
    (net (code "50") (name "Net-(D204-PadC)") (class "Default")
      (node (ref "D204") (pin "C") (pinfunction "C_C") (pintype "passive"))
      (node (ref "J204") (pin "1") (pinfunction "1_1") (pintype "passive"))
      (node (ref "J205") (pin "1") (pinfunction "1_1") (pintype "passive"))
      (node (ref "L204") (pin "P$2") (pinfunction "P$2_P$2") (pintype "bidirectional"))
    )
    (net (code "51") (name "Net-(D701-CC)") (class "Default")
      (node (ref "D701") (pin "3") (pinfunction "CC_3") (pintype "passive"))
      (node (ref "F701") (pin "2") (pinfunction "2_2") (pintype "bidirectional"))
    )
    (net (code "52") (name "Net-(J601A-S)") (class "Default")
      (node (ref "J601") (pin "1") (pinfunction "S_1") (pintype "passive"))
      (node (ref "R602") (pin "P$2") (pinfunction "2_P$2") (pintype "passive"))
    )
    (net (code "53") (name "Net-(J601J-S)") (class "Default")
      (node (ref "J601") (pin "4") (pinfunction "S_4") (pintype "passive"))
      (node (ref "R603") (pin "P$2") (pinfunction "2_P$2") (pintype "passive"))
    )
    (net (code "54") (name "Net-(L401-2)") (class "Default")
      (node (ref "L401") (pin "P$2") (pinfunction "2_P$2") (pintype "passive"))
      (node (ref "U402") (pin "5") (pinfunction "SW_5") (pintype "passive"))
    )
    (net (code "55") (name "Net-(R201-1)") (class "Default")
      (node (ref "R201") (pin "P$1") (pinfunction "1_P$1") (pintype "passive"))
      (node (ref "U201") (pin "20") (pinfunction "B1_20") (pintype "bidirectional"))
    )
    (net (code "56") (name "Net-(R202-1)") (class "Default")
      (node (ref "R202") (pin "P$1") (pinfunction "1_P$1") (pintype "passive"))
      (node (ref "U201") (pin "18") (pinfunction "B2_18") (pintype "bidirectional"))
    )
    (net (code "57") (name "Net-(R203-1)") (class "Default")
      (node (ref "R203") (pin "P$1") (pinfunction "1_P$1") (pintype "passive"))
      (node (ref "U201") (pin "17") (pinfunction "B3_17") (pintype "bidirectional"))
    )
    (net (code "58") (name "Net-(R204-1)") (class "Default")
      (node (ref "R204") (pin "P$1") (pinfunction "1_P$1") (pintype "passive"))
      (node (ref "U201") (pin "16") (pinfunction "B4_16") (pintype "bidirectional"))
    )
    (net (code "59") (name "Net-(R205-2)") (class "Default")
      (node (ref "J202") (pin "4") (pinfunction "4_4") (pintype "passive"))
      (node (ref "R205") (pin "P$2") (pinfunction "2_P$2") (pintype "passive"))
    )
    (net (code "60") (name "Net-(R206-2)") (class "Default")
      (node (ref "J202") (pin "5") (pinfunction "5_5") (pintype "passive"))
      (node (ref "R206") (pin "P$2") (pinfunction "2_P$2") (pintype "passive"))
    )
    (net (code "61") (name "Net-(R207-2)") (class "Default")
      (node (ref "J203") (pin "2") (pinfunction "2_2") (pintype "passive"))
      (node (ref "R207") (pin "P$2") (pinfunction "2_P$2") (pintype "passive"))
    )
    (net (code "62") (name "Net-(R208-2)") (class "Default")
      (node (ref "J203") (pin "4") (pinfunction "4_4") (pintype "passive"))
      (node (ref "R208") (pin "P$2") (pinfunction "2_P$2") (pintype "passive"))
    )
    (net (code "63") (name "Net-(R211-2)") (class "Default")
      (node (ref "J205") (pin "2") (pinfunction "2_2") (pintype "passive"))
      (node (ref "R211") (pin "P$2") (pinfunction "2_P$2") (pintype "passive"))
    )
    (net (code "64") (name "Net-(R212-2)") (class "Default")
      (node (ref "J205") (pin "3") (pinfunction "3_3") (pintype "passive"))
      (node (ref "R212") (pin "P$2") (pinfunction "2_P$2") (pintype "passive"))
    )
    (net (code "65") (name "Net-(R401-1)") (class "Default")
      (node (ref "R401") (pin "P$1") (pinfunction "1_P$1") (pintype "passive"))
      (node (ref "U402") (pin "7") (pinfunction "+IN_7") (pintype "input"))
    )
    (net (code "66") (name "Net-(R402-1)") (class "Default")
      (node (ref "R402") (pin "P$1") (pinfunction "1_P$1") (pintype "passive"))
      (node (ref "R403") (pin "P$2") (pinfunction "2_P$2") (pintype "passive"))
      (node (ref "U402") (pin "8") (pinfunction "-IN_8") (pintype "input"))
    )
    (net (code "67") (name "Net-(R404-2)") (class "Default")
      (node (ref "R404") (pin "P$2") (pinfunction "2_P$2") (pintype "passive"))
      (node (ref "U401") (pin "6") (pinfunction "REXT_6") (pintype "bidirectional"))
    )
    (net (code "68") (name "Net-(R405-2)") (class "Default")
      (node (ref "R405") (pin "P$2") (pinfunction "2_P$2") (pintype "passive"))
      (node (ref "R406") (pin "P$1") (pinfunction "1_P$1") (pintype "passive"))
      (node (ref "U402") (pin "2") (pinfunction "FB_2") (pintype "bidirectional"))
    )
    (net (code "69") (name "Net-(R407-2)") (class "Default")
      (node (ref "LED401") (pin "C") (pinfunction "C_C") (pintype "passive"))
      (node (ref "R407") (pin "P$2") (pinfunction "2_P$2") (pintype "passive"))
    )
    (net (code "70") (name "Net-(R408-1)") (class "Default")
      (node (ref "R408") (pin "P$1") (pinfunction "1_P$1") (pintype "passive"))
      (node (ref "R409") (pin "P$2") (pinfunction "2_P$2") (pintype "passive"))
    )
    (net (code "71") (name "Net-(R408-2)") (class "Default")
      (node (ref "LED402") (pin "C") (pinfunction "C_C") (pintype "passive"))
      (node (ref "R408") (pin "P$2") (pinfunction "2_P$2") (pintype "passive"))
    )
    (net (code "72") (name "Net-(R410-2)") (class "Default")
      (node (ref "LED403") (pin "C") (pinfunction "C_C") (pintype "passive"))
      (node (ref "R410") (pin "P$2") (pinfunction "2_P$2") (pintype "passive"))
    )
    (net (code "73") (name "Net-(R411-1)") (class "Default")
      (node (ref "J402") (pin "2") (pinfunction "2_2") (pintype "passive"))
      (node (ref "R411") (pin "P$1") (pinfunction "1_P$1") (pintype "passive"))
    )
    (net (code "74") (name "Net-(R502-1)") (class "Default")
      (node (ref "R502") (pin "P$1") (pinfunction "1_P$1") (pintype "passive"))
      (node (ref "U501") (pin "28") (pinfunction "PB2_28") (pintype "bidirectional"))
    )
    (net (code "75") (name "Net-(R601-2)") (class "Default")
      (node (ref "D602") (pin "C") (pinfunction "C_C") (pintype "passive"))
      (node (ref "R601") (pin "P$2") (pinfunction "2_P$2") (pintype "passive"))
      (node (ref "R603") (pin "P$1") (pinfunction "1_P$1") (pintype "passive"))
      (node (ref "U601") (pin "3") (pinfunction "2Y_3") (pintype "bidirectional"))
    )
    (net (code "76") (name "Net-(R604-1)") (class "Default")
      (node (ref "R604") (pin "P$1") (pinfunction "1_P$1") (pintype "passive"))
      (node (ref "R605") (pin "P$2") (pinfunction "2_P$2") (pintype "passive"))
    )
    (net (code "77") (name "Net-(R701-2)") (class "Default")
      (node (ref "L702") (pin "P$2") (pinfunction "P$2_P$2") (pintype "bidirectional"))
      (node (ref "R701") (pin "P$2") (pinfunction "2_P$2") (pintype "passive"))
    )
    (net (code "78") (name "Net-(R702-2)") (class "Default")
      (node (ref "L701") (pin "P$2") (pinfunction "P$2_P$2") (pintype "bidirectional"))
      (node (ref "R702") (pin "P$2") (pinfunction "2_P$2") (pintype "passive"))
    )
    (net (code "79") (name "Net-(R703-1)") (class "Default")
      (node (ref "J701") (pin "4") (pinfunction "4_4") (pintype "passive"))
      (node (ref "L702") (pin "P$1") (pinfunction "P$1_P$1") (pintype "bidirectional"))
      (node (ref "R703") (pin "P$1") (pinfunction "1_P$1") (pintype "passive"))
    )
    (net (code "80") (name "Net-(R704-1)") (class "Default")
      (node (ref "J701") (pin "3") (pinfunction "3_3") (pintype "passive"))
      (node (ref "L701") (pin "P$1") (pinfunction "P$1_P$1") (pintype "bidirectional"))
      (node (ref "R704") (pin "P$1") (pinfunction "1_P$1") (pintype "passive"))
    )
    (net (code "81") (name "Net-(U401-OUT0)") (class "Default")
      (node (ref "U401") (pin "9") (pinfunction "OUT0_9") (pintype "open_collector"))
      (node (ref "U403") (pin "C1") (pinfunction "C_C1") (pintype "passive"))
    )
    (net (code "82") (name "Net-(U401-OUT1)") (class "Default")
      (node (ref "U401") (pin "8") (pinfunction "OUT1_8") (pintype "open_collector"))
      (node (ref "U403") (pin "C2") (pinfunction "C_C2") (pintype "passive"))
    )
    (net (code "83") (name "Net-(U401-OUT2)") (class "Default")
      (node (ref "U401") (pin "7") (pinfunction "OUT2_7") (pintype "open_collector"))
      (node (ref "U403") (pin "C3") (pinfunction "C_C3") (pintype "passive"))
    )
    (net (code "84") (name "PPM_INPUT") (class "Default")
      (node (ref "D601") (pin "C") (pinfunction "C_C") (pintype "passive"))
      (node (ref "R602") (pin "P$1") (pinfunction "1_P$1") (pintype "passive"))
      (node (ref "U501") (pin "41") (pinfunction "PA8_41") (pintype "bidirectional"))
      (node (ref "U601") (pin "2") (pinfunction "1A_2") (pintype "bidirectional"))
    )
    (net (code "85") (name "PRESSURE_SENS") (class "Default")
      (node (ref "C202") (pin "P$1") (pinfunction "1_P$1") (pintype "passive"))
      (node (ref "R209") (pin "P$1") (pinfunction "1_P$1") (pintype "passive"))
      (node (ref "R210") (pin "P$2") (pinfunction "2_P$2") (pintype "passive"))
      (node (ref "U501") (pin "11") (pinfunction "PC3_11") (pintype "bidirectional"))
    )
    (net (code "86") (name "PRESSURE_SENS_IN") (class "Default")
      (node (ref "ADC_PR") (pin "P$1") (pinfunction "P$1_P$1") (pintype "passive"))
      (node (ref "J204") (pin "2") (pinfunction "2_2") (pintype "passive"))
      (node (ref "R209") (pin "P$2") (pinfunction "2_P$2") (pintype "passive"))
    )
    (net (code "87") (name "RPI-I2C_SCL") (class "Default")
      (node (ref "R211") (pin "P$1") (pinfunction "1_P$1") (pintype "passive"))
      (node (ref "U101") (pin "P$5") (pinfunction "GPIO3_P$5") (pintype "bidirectional"))
      (node (ref "U401") (pin "3") (pinfunction "SCL_3") (pintype "bidirectional"))
    )
    (net (code "88") (name "RPI-I2C_SDA") (class "Default")
      (node (ref "R212") (pin "P$1") (pinfunction "1_P$1") (pintype "passive"))
      (node (ref "U101") (pin "P$3") (pinfunction "GPIO2_P$3") (pintype "bidirectional"))
      (node (ref "U401") (pin "2") (pinfunction "SDA_2") (pintype "bidirectional"))
    )
    (net (code "89") (name "RPI-UART_RX") (class "Default")
      (node (ref "U101") (pin "P$10") (pinfunction "GPIO15_P$10") (pintype "bidirectional"))
      (node (ref "U201") (pin "4") (pinfunction "A3_4") (pintype "bidirectional"))
    )
    (net (code "90") (name "RPI-UART_TX") (class "Default")
      (node (ref "U101") (pin "P$8") (pinfunction "GPIO14_P$8") (pintype "bidirectional"))
      (node (ref "U201") (pin "5") (pinfunction "A4_5") (pintype "bidirectional"))
    )
    (net (code "91") (name "RSSI_IN") (class "Default")
      (node (ref "R601") (pin "P$1") (pinfunction "1_P$1") (pintype "passive"))
      (node (ref "U501") (pin "21") (pinfunction "PA5_21") (pintype "bidirectional"))
      (node (ref "U501") (pin "45") (pinfunction "PA12_45") (pintype "bidirectional"))
    )
    (net (code "92") (name "RX-VDD_5V5") (class "Default")
      (node (ref "F701") (pin "1") (pinfunction "1_1") (pintype "bidirectional"))
      (node (ref "J601") (pin "2") (pinfunction "S_2") (pintype "passive"))
    )
    (net (code "93") (name "SAFETY") (class "Default")
      (node (ref "J402") (pin "3") (pinfunction "3_3") (pintype "passive"))
      (node (ref "R412") (pin "P$1") (pinfunction "1_P$1") (pintype "passive"))
      (node (ref "U501") (pin "38") (pinfunction "PC7_38") (pintype "bidirectional"))
    )
    (net (code "94") (name "SBUS_INPUT") (class "Default")
      (node (ref "U501") (pin "30") (pinfunction "PB11_30") (pintype "bidirectional"))
      (node (ref "U601") (pin "6") (pinfunction "1Y_6") (pintype "bidirectional"))
    )
    (net (code "95") (name "SBUS_OUTPUT") (class "Default")
      (node (ref "U501") (pin "29") (pinfunction "PB10_29") (pintype "bidirectional"))
      (node (ref "U601") (pin "5") (pinfunction "2A_5") (pintype "bidirectional"))
    )
    (net (code "96") (name "SERIAL1_RX") (class "Default")
      (node (ref "J201") (pin "3") (pinfunction "3_3") (pintype "passive"))
      (node (ref "R203") (pin "P$2") (pinfunction "2_P$2") (pintype "passive"))
      (node (ref "S1RX") (pin "P$1") (pinfunction "P$1_P$1") (pintype "passive"))
    )
    (net (code "97") (name "SERIAL1_TX") (class "Default")
      (node (ref "J201") (pin "2") (pinfunction "2_2") (pintype "passive"))
      (node (ref "R204") (pin "P$2") (pinfunction "2_P$2") (pintype "passive"))
      (node (ref "S1TX") (pin "P$1") (pinfunction "P$1_P$1") (pintype "passive"))
    )
    (net (code "98") (name "SERIAL2_RX") (class "Default")
      (node (ref "J202") (pin "3") (pinfunction "3_3") (pintype "passive"))
      (node (ref "R201") (pin "P$2") (pinfunction "2_P$2") (pintype "passive"))
      (node (ref "S2RX") (pin "P$1") (pinfunction "P$1_P$1") (pintype "passive"))
    )
    (net (code "99") (name "SERIAL2_TX") (class "Default")
      (node (ref "J202") (pin "2") (pinfunction "2_2") (pintype "passive"))
      (node (ref "R202") (pin "P$2") (pinfunction "2_P$2") (pintype "passive"))
      (node (ref "S2TX") (pin "P$1") (pinfunction "P$1_P$1") (pintype "passive"))
    )
    (net (code "100") (name "VDD_3V3_SENSORS") (class "Default")
      (node (ref "C301") (pin "P$1") (pinfunction "1_P$1") (pintype "passive"))
      (node (ref "C302") (pin "P$1") (pinfunction "1_P$1") (pintype "passive"))
      (node (ref "C303") (pin "P$1") (pinfunction "1_P$1") (pintype "passive"))
      (node (ref "C306") (pin "P$1") (pinfunction "1_P$1") (pintype "passive"))
      (node (ref "C307") (pin "P$1") (pinfunction "1_P$1") (pintype "passive"))
      (node (ref "C308") (pin "P$1") (pinfunction "1_P$1") (pintype "passive"))
      (node (ref "C311") (pin "P$1") (pinfunction "1_P$1") (pintype "passive"))
      (node (ref "C313") (pin "P$1") (pinfunction "1_P$1") (pintype "passive"))
      (node (ref "C314") (pin "P$1") (pinfunction "1_P$1") (pintype "passive"))
      (node (ref "C703") (pin "P$1") (pinfunction "1_P$1") (pintype "passive"))
      (node (ref "C704") (pin "P$1") (pinfunction "1_P$1") (pintype "passive"))
      (node (ref "U301") (pin "1") (pinfunction "VDD_IO_1") (pintype "bidirectional"))
      (node (ref "U301") (pin "15") (pinfunction "RES_P15_VDD_15") (pintype "bidirectional"))
      (node (ref "U301") (pin "16") (pinfunction "VDD_16") (pintype "bidirectional"))
      (node (ref "U302") (pin "1") (pinfunction "VDD_IO_1") (pintype "bidirectional"))
      (node (ref "U302") (pin "15") (pinfunction "VDD_15") (pintype "bidirectional"))
      (node (ref "U302") (pin "16") (pinfunction "VDD_16") (pintype "bidirectional"))
      (node (ref "U304") (pin "1") (pinfunction "VDD_IO_1") (pintype "bidirectional"))
      (node (ref "U304") (pin "14") (pinfunction "VDD_14") (pintype "bidirectional"))
      (node (ref "U305") (pin "13") (pinfunction "VDD_13") (pintype "bidirectional"))
      (node (ref "U306") (pin "1") (pinfunction "VDD_1") (pintype "bidirectional"))
      (node (ref "U701") (pin "7") (pinfunction "VOUT2_7") (pintype "bidirectional"))
    )
    (net (code "101") (name "VDD_5V_BRICK") (class "Default")
      (node (ref "D701") (pin "1") (pinfunction "A1_1") (pintype "passive"))
      (node (ref "D702") (pin "1") (pinfunction "A1_1") (pintype "passive"))
      (node (ref "D703") (pin "C") (pinfunction "C_C") (pintype "passive"))
      (node (ref "J701") (pin "1") (pinfunction "1_1") (pintype "passive"))
      (node (ref "J701") (pin "2") (pinfunction "2_2") (pintype "passive"))
      (node (ref "VDD_5V_BRICK") (pin "P$1") (pinfunction "P$1_P$1") (pintype "passive"))
    )
    (net (code "102") (name "VDD_5V_IN") (class "Default")
      (node (ref "C402") (pin "P$1") (pinfunction "1_P$1") (pintype "passive"))
      (node (ref "C701") (pin "P$1") (pinfunction "1_P$1") (pintype "passive"))
      (node (ref "C705") (pin "P$1") (pinfunction "1_P$1") (pintype "passive"))
      (node (ref "D702") (pin "3") (pinfunction "CC_3") (pintype "passive"))
      (node (ref "F702") (pin "1") (pinfunction "1_1") (pintype "bidirectional"))
      (node (ref "L401") (pin "P$1") (pinfunction "1_P$1") (pintype "passive"))
      (node (ref "LED401") (pin "A") (pinfunction "A_A") (pintype "passive"))
      (node (ref "LED402") (pin "A") (pinfunction "A_A") (pintype "passive"))
      (node (ref "LED403") (pin "A") (pinfunction "A_A") (pintype "passive"))
      (node (ref "R705") (pin "P$2") (pinfunction "2_P$2") (pintype "passive"))
      (node (ref "U101") (pin "P$2") (pinfunction "5V_P$2") (pintype "bidirectional"))
      (node (ref "U101") (pin "P$4") (pinfunction "5V_P$4") (pintype "bidirectional"))
      (node (ref "U402") (pin "3") (pinfunction "VIN_3") (pintype "power_in"))
      (node (ref "U403") (pin "A1") (pinfunction "A_A1") (pintype "passive"))
      (node (ref "U403") (pin "A2") (pinfunction "A_A2") (pintype "passive"))
      (node (ref "U403") (pin "A3") (pinfunction "A_A3") (pintype "passive"))
      (node (ref "U701") (pin "1") (pinfunction "VIN_1") (pintype "bidirectional"))
      (node (ref "U701") (pin "4") (pinfunction "EN2_4") (pintype "bidirectional"))
      (node (ref "U701") (pin "5") (pinfunction "EN1_5") (pintype "bidirectional"))
      (node (ref "VDD_5V_IN") (pin "P$1") (pinfunction "P$1_P$1") (pintype "passive"))
    )
    (net (code "103") (name "VDD_5V_PERIPH") (class "Default")
      (node (ref "F702") (pin "2") (pinfunction "2_2") (pintype "bidirectional"))
      (node (ref "L201") (pin "P$1") (pinfunction "P$1_P$1") (pintype "bidirectional"))
      (node (ref "L202") (pin "P$1") (pinfunction "P$1_P$1") (pintype "bidirectional"))
      (node (ref "L203") (pin "P$1") (pinfunction "P$1_P$1") (pintype "bidirectional"))
      (node (ref "L204") (pin "P$1") (pinfunction "P$1_P$1") (pintype "bidirectional"))
    )
    (net (code "104") (name "VDD_5V_SENS") (class "Default")
      (node (ref "R705") (pin "P$1") (pinfunction "1_P$1") (pintype "passive"))
      (node (ref "R706") (pin "P$1") (pinfunction "1_P$1") (pintype "passive"))
      (node (ref "U501") (pin "10") (pinfunction "PC2_10") (pintype "bidirectional"))
    )
    (net (code "105") (name "VDD_SERVO") (class "Default")
      (node (ref "D701") (pin "2") (pinfunction "A2_2") (pintype "passive"))
      (node (ref "D702") (pin "2") (pinfunction "A2_2") (pintype "passive"))
      (node (ref "D704") (pin "C") (pinfunction "C_C") (pintype "passive"))
      (node (ref "J601") (pin "11") (pinfunction "S_11") (pintype "passive"))
      (node (ref "J601") (pin "14") (pinfunction "S_14") (pintype "passive"))
      (node (ref "J601") (pin "17") (pinfunction "S_17") (pintype "passive"))
      (node (ref "J601") (pin "20") (pinfunction "S_20") (pintype "passive"))
      (node (ref "J601") (pin "23") (pinfunction "S_23") (pintype "passive"))
      (node (ref "J601") (pin "26") (pinfunction "S_26") (pintype "passive"))
      (node (ref "J601") (pin "29") (pinfunction "S_29") (pintype "passive"))
      (node (ref "J601") (pin "5") (pinfunction "S_5") (pintype "passive"))
      (node (ref "J601") (pin "8") (pinfunction "S_8") (pintype "passive"))
      (node (ref "R604") (pin "P$2") (pinfunction "2_P$2") (pintype "passive"))
      (node (ref "VDD_SERVO") (pin "P$1") (pinfunction "P$1_P$1") (pintype "passive"))
    )
    (net (code "106") (name "VDD_SERVO_SENS") (class "Default")
      (node (ref "R605") (pin "P$1") (pinfunction "1_P$1") (pintype "passive"))
      (node (ref "R606") (pin "P$2") (pinfunction "2_P$2") (pintype "passive"))
      (node (ref "U501") (pin "20") (pinfunction "PA4_20") (pintype "bidirectional"))
    )
    (net (code "107") (name "unconnected-(J201-Pad4)") (class "Default")
      (node (ref "J201") (pin "4") (pinfunction "4_4") (pintype "passive"))
    )
    (net (code "108") (name "unconnected-(J201-Pad5)") (class "Default")
      (node (ref "J201") (pin "5") (pinfunction "5_5") (pintype "passive"))
    )
    (net (code "109") (name "unconnected-(JX502A-S-Pad10)") (class "Default")
      (node (ref "JX502") (pin "10") (pinfunction "S_10") (pintype "passive"))
    )
    (net (code "110") (name "unconnected-(JX502F-S-Pad8)") (class "Default")
      (node (ref "JX502") (pin "8") (pinfunction "S_8") (pintype "passive"))
    )
    (net (code "111") (name "unconnected-(U101-3V3-PadP$1)") (class "Default")
      (node (ref "U101") (pin "P$1") (pinfunction "3V3_P$1") (pintype "bidirectional"))
    )
    (net (code "112") (name "unconnected-(U101-3V3-PadP$17)") (class "Default")
      (node (ref "U101") (pin "P$17") (pinfunction "3V3_P$17") (pintype "bidirectional"))
    )
    (net (code "113") (name "unconnected-(U101-GPIO8-PadP$24)") (class "Default")
      (node (ref "U101") (pin "P$24") (pinfunction "GPIO8_P$24") (pintype "bidirectional"))
    )
    (net (code "114") (name "unconnected-(U101-GPIO13-PadP$33)") (class "Default")
      (node (ref "U101") (pin "P$33") (pinfunction "GPIO13_P$33") (pintype "bidirectional"))
    )
    (net (code "115") (name "unconnected-(U101-GPIO16-PadP$36)") (class "Default")
      (node (ref "U101") (pin "P$36") (pinfunction "GPIO16_P$36") (pintype "bidirectional"))
    )
    (net (code "116") (name "unconnected-(U101-GPIO19-PadP$35)") (class "Default")
      (node (ref "U101") (pin "P$35") (pinfunction "GPIO19_P$35") (pintype "bidirectional"))
    )
    (net (code "117") (name "unconnected-(U101-GPIO20-PadP$38)") (class "Default")
      (node (ref "U101") (pin "P$38") (pinfunction "GPIO20_P$38") (pintype "bidirectional"))
    )
    (net (code "118") (name "unconnected-(U101-GPIO21-PadP$40)") (class "Default")
      (node (ref "U101") (pin "P$40") (pinfunction "GPIO21_P$40") (pintype "bidirectional"))
    )
    (net (code "119") (name "unconnected-(U101-GPIO26-PadP$37)") (class "Default")
      (node (ref "U101") (pin "P$37") (pinfunction "GPIO26_P$37") (pintype "bidirectional"))
    )
    (net (code "120") (name "unconnected-(U101-ID_SC*-PadP$28)") (class "Default")
      (node (ref "U101") (pin "P$28") (pinfunction "ID_SC*_P$28") (pintype "bidirectional"))
    )
    (net (code "121") (name "unconnected-(U101-ID_SD*-PadP$27)") (class "Default")
      (node (ref "U101") (pin "P$27") (pinfunction "ID_SD*_P$27") (pintype "bidirectional"))
    )
    (net (code "122") (name "unconnected-(U201-A5-Pad6)") (class "Default")
      (node (ref "U201") (pin "6") (pinfunction "A5_6") (pintype "bidirectional"))
    )
    (net (code "123") (name "unconnected-(U201-A6-Pad7)") (class "Default")
      (node (ref "U201") (pin "7") (pinfunction "A6_7") (pintype "bidirectional"))
    )
    (net (code "124") (name "unconnected-(U201-A7-Pad8)") (class "Default")
      (node (ref "U201") (pin "8") (pinfunction "A7_8") (pintype "bidirectional"))
    )
    (net (code "125") (name "unconnected-(U201-A8-Pad9)") (class "Default")
      (node (ref "U201") (pin "9") (pinfunction "A8_9") (pintype "bidirectional"))
    )
    (net (code "126") (name "unconnected-(U201-B5-Pad15)") (class "Default")
      (node (ref "U201") (pin "15") (pinfunction "B5_15") (pintype "bidirectional"))
    )
    (net (code "127") (name "unconnected-(U201-B6-Pad14)") (class "Default")
      (node (ref "U201") (pin "14") (pinfunction "B6_14") (pintype "bidirectional"))
    )
    (net (code "128") (name "unconnected-(U201-B7-Pad13)") (class "Default")
      (node (ref "U201") (pin "13") (pinfunction "B7_13") (pintype "bidirectional"))
    )
    (net (code "129") (name "unconnected-(U201-B8-Pad12)") (class "Default")
      (node (ref "U201") (pin "12") (pinfunction "B8_12") (pintype "bidirectional"))
    )
    (net (code "130") (name "unconnected-(U301-INT1-Pad7)") (class "Default")
      (node (ref "U301") (pin "7") (pinfunction "INT1_7") (pintype "output"))
    )
    (net (code "131") (name "unconnected-(U302-DEN-Pad8)") (class "Default")
      (node (ref "U302") (pin "8") (pinfunction "DEN_8") (pintype "bidirectional"))
    )
    (net (code "132") (name "unconnected-(U302-INT1-Pad7)") (class "Default")
      (node (ref "U302") (pin "7") (pinfunction "INT1_7") (pintype "bidirectional"))
    )
    (net (code "133") (name "unconnected-(U305-AUX_CL-Pad7)") (class "Default")
      (node (ref "U305") (pin "7") (pinfunction "AUX_CL_7") (pintype "bidirectional"))
    )
    (net (code "134") (name "unconnected-(U305-AUX_DA-Pad6)") (class "Default")
      (node (ref "U305") (pin "6") (pinfunction "AUX_DA_6") (pintype "bidirectional"))
    )
    (net (code "135") (name "unconnected-(U305-CLKOUT-Pad22)") (class "Default")
      (node (ref "U305") (pin "22") (pinfunction "CLKOUT_22") (pintype "bidirectional"))
    )
    (net (code "136") (name "unconnected-(U305-FSYNC-Pad11)") (class "Default")
      (node (ref "U305") (pin "11") (pinfunction "FSYNC_11") (pintype "bidirectional"))
    )
    (net (code "137") (name "unconnected-(U305-NC1-Pad2)") (class "Default")
      (node (ref "U305") (pin "2") (pinfunction "NC1_2") (pintype "bidirectional"))
    )
    (net (code "138") (name "unconnected-(U305-NC2-Pad3)") (class "Default")
      (node (ref "U305") (pin "3") (pinfunction "NC2_3") (pintype "bidirectional"))
    )
    (net (code "139") (name "unconnected-(U305-NC3-Pad4)") (class "Default")
      (node (ref "U305") (pin "4") (pinfunction "NC3_4") (pintype "bidirectional"))
    )
    (net (code "140") (name "unconnected-(U305-NC4-Pad5)") (class "Default")
      (node (ref "U305") (pin "5") (pinfunction "NC4_5") (pintype "bidirectional"))
    )
    (net (code "141") (name "unconnected-(U305-NC5-Pad14)") (class "Default")
      (node (ref "U305") (pin "14") (pinfunction "NC5_14") (pintype "bidirectional"))
    )
    (net (code "142") (name "unconnected-(U305-NC6-Pad15)") (class "Default")
      (node (ref "U305") (pin "15") (pinfunction "NC6_15") (pintype "bidirectional"))
    )
    (net (code "143") (name "unconnected-(U305-NC7-Pad16)") (class "Default")
      (node (ref "U305") (pin "16") (pinfunction "NC7_16") (pintype "bidirectional"))
    )
    (net (code "144") (name "unconnected-(U305-NC8-Pad17)") (class "Default")
      (node (ref "U305") (pin "17") (pinfunction "NC8_17") (pintype "bidirectional"))
    )
    (net (code "145") (name "unconnected-(U305-RESV1-Pad19)") (class "Default")
      (node (ref "U305") (pin "19") (pinfunction "RESV1_19") (pintype "bidirectional"))
    )
    (net (code "146") (name "unconnected-(U305-RESV2-Pad21)") (class "Default")
      (node (ref "U305") (pin "21") (pinfunction "RESV2_21") (pintype "bidirectional"))
    )
    (net (code "147") (name "unconnected-(U306-CSB1-Pad4)") (class "Default")
      (node (ref "U306") (pin "4") (pinfunction "CSB1_4") (pintype "bidirectional"))
    )
    (net (code "148") (name "unconnected-(U501B-PC8-Pad39)") (class "Default")
      (node (ref "U501") (pin "39") (pinfunction "PC8_39") (pintype "bidirectional"))
    )
    (net (code "149") (name "unconnected-(U501B-PC9-Pad40)") (class "Default")
      (node (ref "U501") (pin "40") (pinfunction "PC9_40") (pintype "bidirectional"))
    )
    (net (code "150") (name "unconnected-(U501B-PC10-Pad51)") (class "Default")
      (node (ref "U501") (pin "51") (pinfunction "PC10_51") (pintype "bidirectional"))
    )
    (net (code "151") (name "unconnected-(U501B-PC11-Pad52)") (class "Default")
      (node (ref "U501") (pin "52") (pinfunction "PC11_52") (pintype "bidirectional"))
    )
    (net (code "152") (name "unconnected-(U501B-PC12-Pad53)") (class "Default")
      (node (ref "U501") (pin "53") (pinfunction "PC12_53") (pintype "bidirectional"))
    )
    (net (code "153") (name "unconnected-(U501B-PC13-Pad2)") (class "Default")
      (node (ref "U501") (pin "2") (pinfunction "PC13_2") (pintype "bidirectional"))
    )
    (net (code "154") (name "unconnected-(U501B-PC14-Pad3)") (class "Default")
      (node (ref "U501") (pin "3") (pinfunction "PC14_3") (pintype "bidirectional"))
    )
    (net (code "155") (name "unconnected-(U501B-PC15-Pad4)") (class "Default")
      (node (ref "U501") (pin "4") (pinfunction "PC15_4") (pintype "bidirectional"))
    )
    (net (code "156") (name "unconnected-(U501E-PD2-Pad54)") (class "Default")
      (node (ref "U501") (pin "54") (pinfunction "PD2_54") (pintype "bidirectional"))
    )
    (net (code "157") (name "unconnected-(U501F-PA11-Pad44)") (class "Default")
      (node (ref "U501") (pin "44") (pinfunction "PA11_44") (pintype "bidirectional"))
    )
    (net (code "158") (name "unconnected-(U501H-PB12-Pad33)") (class "Default")
      (node (ref "U501") (pin "33") (pinfunction "PB12_33") (pintype "bidirectional"))
    )
    (net (code "159") (name "~{ACCEL_MAG_CS}") (class "Default")
      (node (ref "U101") (pin "P$15") (pinfunction "GPIO22_P$15") (pintype "bidirectional"))
      (node (ref "U304") (pin "8") (pinfunction "CS_8") (pintype "bidirectional"))
    )
    (net (code "160") (name "~{BARO_CS}") (class "Default")
      (node (ref "U101") (pin "P$16") (pinfunction "GPIO23_P$16") (pintype "bidirectional"))
      (node (ref "U306") (pin "5") (pinfunction "CSB2_5") (pintype "bidirectional"))
    )
    (net (code "161") (name "~{FRAM_CS}") (class "Default")
      (node (ref "U101") (pin "P$29") (pinfunction "GPIO5_P$29") (pintype "bidirectional"))
      (node (ref "U102") (pin "1") (pinfunction "~{S}_1") (pintype "bidirectional"))
    )
    (net (code "162") (name "~{GYRO_CS}") (class "Default")
      (node (ref "U101") (pin "P$32") (pinfunction "GPIO12_P$32") (pintype "bidirectional"))
      (node (ref "U301") (pin "5") (pinfunction "CS_5") (pintype "input"))
      (node (ref "U302") (pin "5") (pinfunction "CS_5") (pintype "bidirectional"))
    )
    (net (code "163") (name "~{IO-LED_AMBER}") (class "Default")
      (node (ref "R409") (pin "P$1") (pinfunction "1_P$1") (pintype "passive"))
      (node (ref "U501") (pin "36") (pinfunction "PB15_36") (pintype "bidirectional"))
    )
    (net (code "164") (name "~{IO-LED_BLUE}") (class "Default")
      (node (ref "R410") (pin "P$1") (pinfunction "1_P$1") (pintype "passive"))
      (node (ref "U501") (pin "35") (pinfunction "PB14_35") (pintype "bidirectional"))
    )
    (net (code "165") (name "~{IO-LED_SAFETY}") (class "Default")
      (node (ref "R411") (pin "P$2") (pinfunction "2_P$2") (pintype "passive"))
      (node (ref "U501") (pin "34") (pinfunction "PB13_34") (pintype "bidirectional"))
    )
    (net (code "166") (name "~{MPU_CS}") (class "Default")
      (node (ref "U101") (pin "P$22") (pinfunction "GPIO25_P$22") (pintype "bidirectional"))
      (node (ref "U305") (pin "8") (pinfunction "/CS_8") (pintype "bidirectional"))
    )
    (net (code "167") (name "~{SBUS_OUTPUT_EN}") (class "Default")
      (node (ref "U501") (pin "37") (pinfunction "PC6_37") (pintype "bidirectional"))
      (node (ref "U601") (pin "7") (pinfunction "~{2OE}_7") (pintype "input"))
    )
  )
)
